# customESC_Test_Board.net
KiCad netlist of a schematic drawn in EAGLE
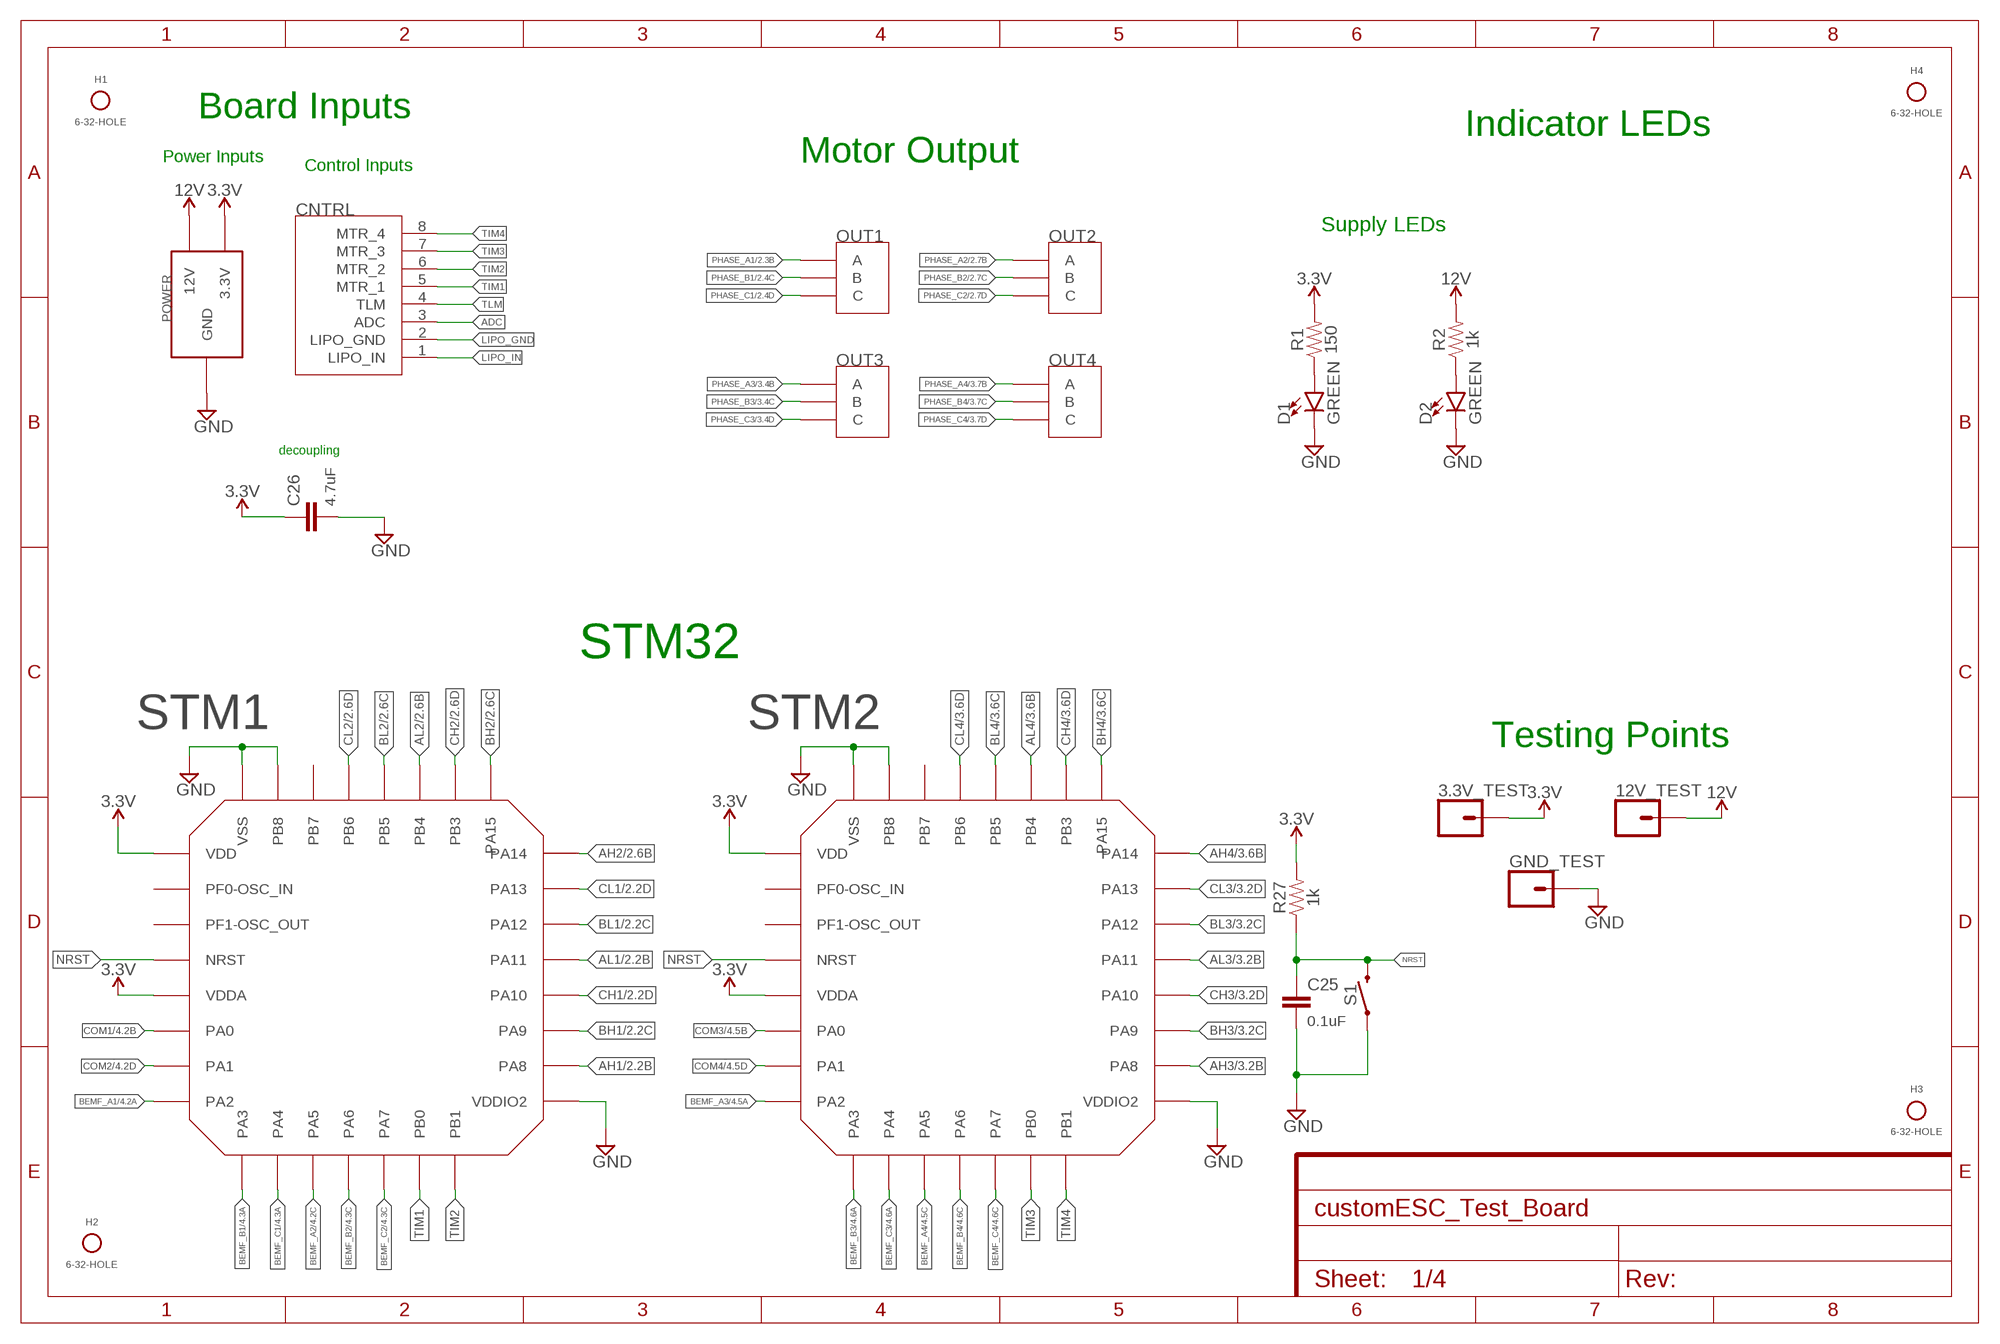
[diagram p0: schematic, sheet 1]
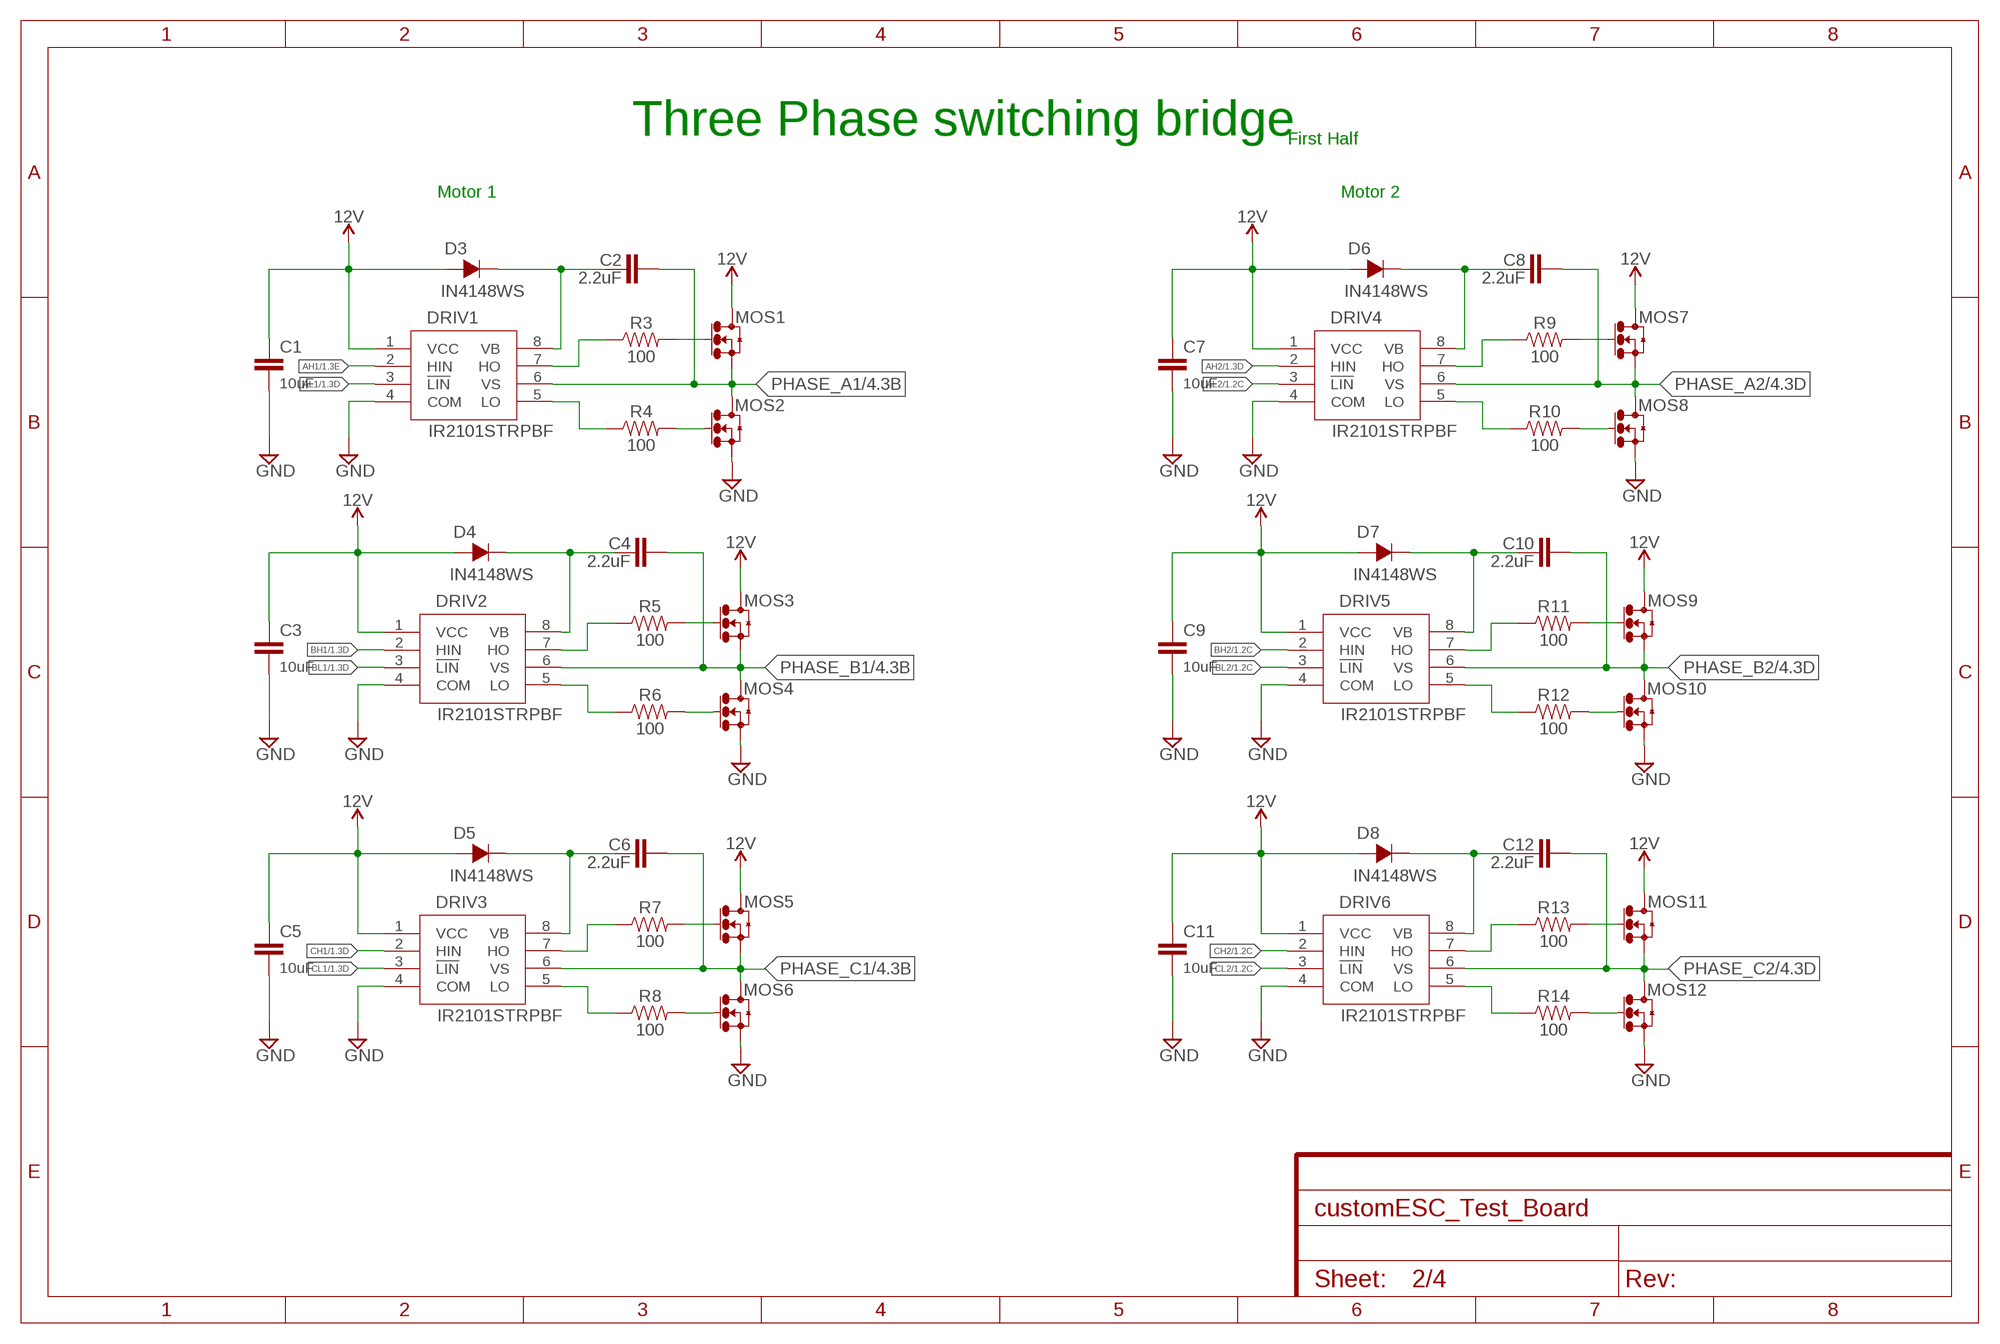
[diagram p1: schematic, sheet 2]
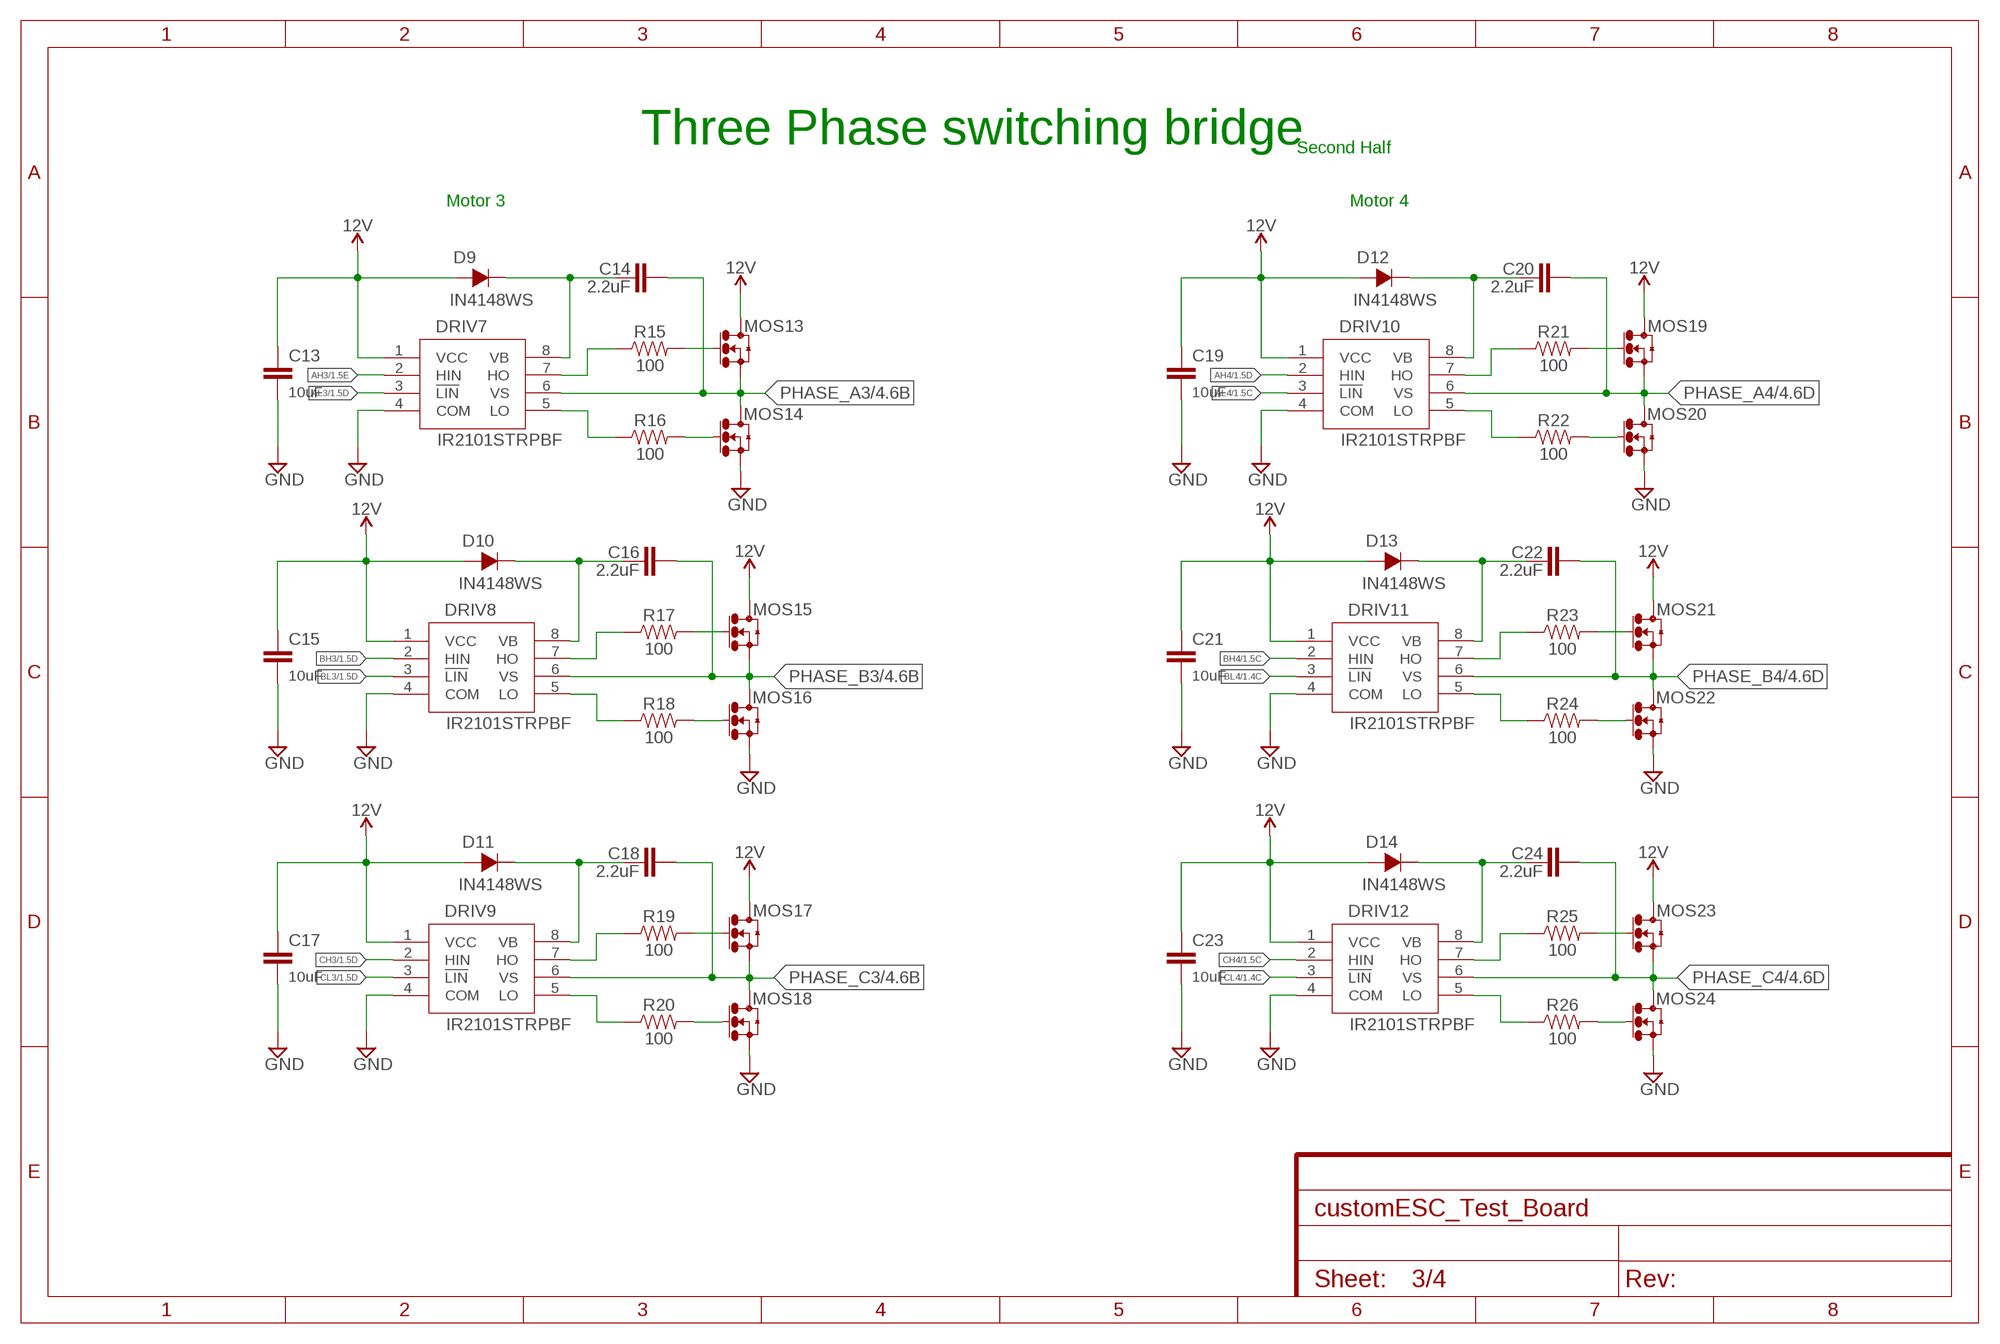
[diagram p2: schematic, sheet 3]
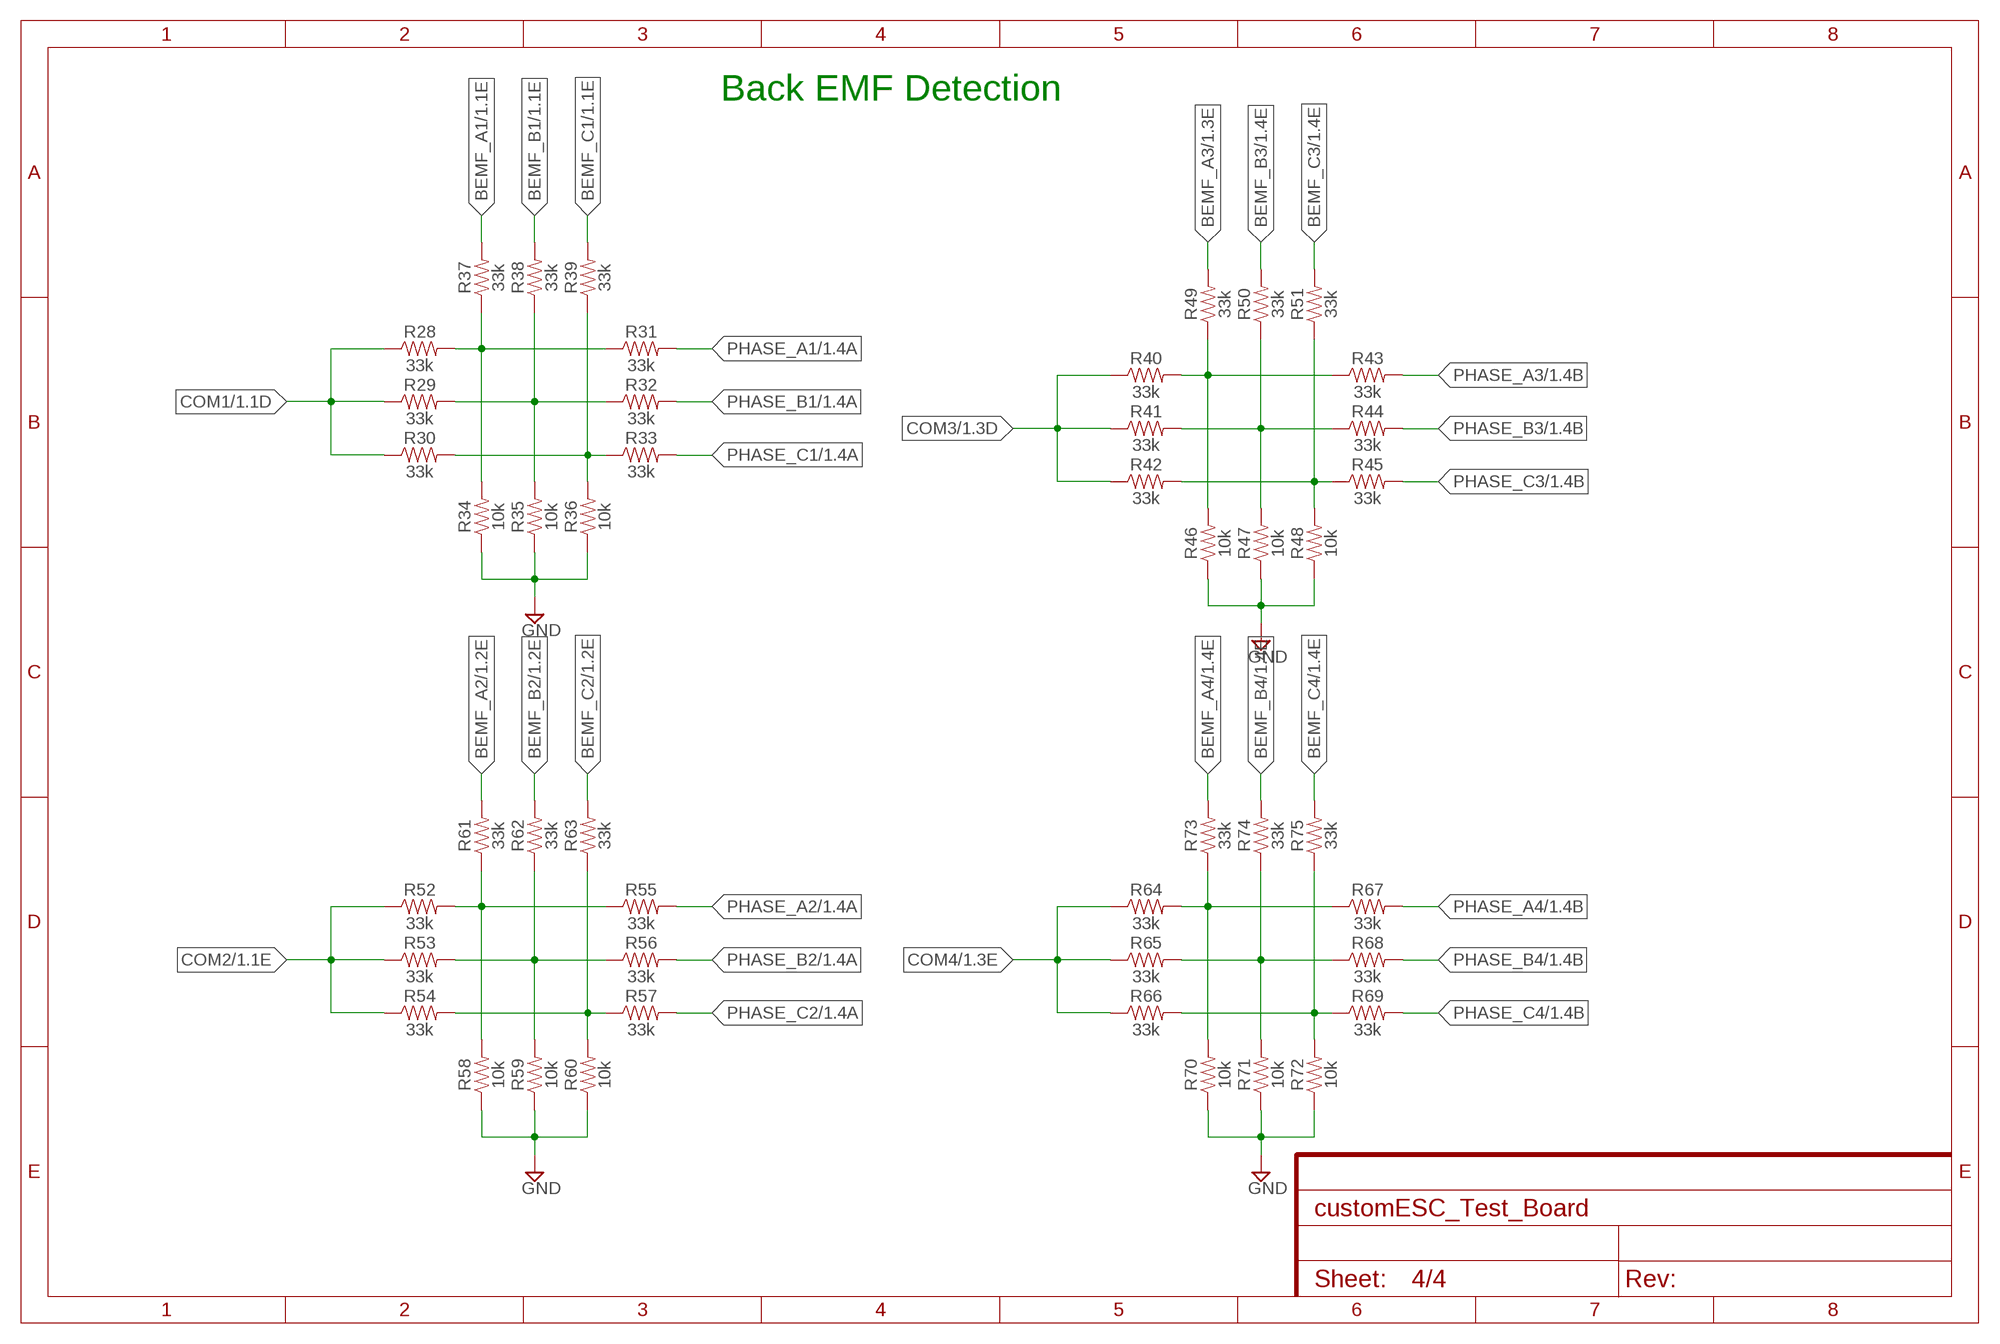
[diagram p3: schematic, sheet 4]

(export (version "E")
  (design (tool "Eeschema 10.0.6"))
  (components
    (comp (ref "C1")
      (value "10uF")
      (footprint "eagle-import:0603")
      (libsource (lib "eagle-import") (part "10UF-0603-6.3V-20%"))
    )
    (comp (ref "C2")
      (value "2.2uF")
      (footprint "eagle-import:0603")
      (libsource (lib "eagle-import") (part "10UF-0603-6.3V-20%"))
    )
    (comp (ref "C3")
      (value "10uF")
      (footprint "eagle-import:0603")
      (libsource (lib "eagle-import") (part "10UF-0603-6.3V-20%"))
    )
    (comp (ref "C4")
      (value "2.2uF")
      (footprint "eagle-import:0603")
      (libsource (lib "eagle-import") (part "10UF-0603-6.3V-20%"))
    )
    (comp (ref "C5")
      (value "10uF")
      (footprint "eagle-import:0603")
      (libsource (lib "eagle-import") (part "10UF-0603-6.3V-20%"))
    )
    (comp (ref "C6")
      (value "2.2uF")
      (footprint "eagle-import:0603")
      (libsource (lib "eagle-import") (part "10UF-0603-6.3V-20%"))
    )
    (comp (ref "C7")
      (value "10uF")
      (footprint "eagle-import:0603")
      (libsource (lib "eagle-import") (part "10UF-0603-6.3V-20%"))
    )
    (comp (ref "C8")
      (value "2.2uF")
      (footprint "eagle-import:0603")
      (libsource (lib "eagle-import") (part "10UF-0603-6.3V-20%"))
    )
    (comp (ref "C9")
      (value "10uF")
      (footprint "eagle-import:0603")
      (libsource (lib "eagle-import") (part "10UF-0603-6.3V-20%"))
    )
    (comp (ref "C10")
      (value "2.2uF")
      (footprint "eagle-import:0603")
      (libsource (lib "eagle-import") (part "10UF-0603-6.3V-20%"))
    )
    (comp (ref "C11")
      (value "10uF")
      (footprint "eagle-import:0603")
      (libsource (lib "eagle-import") (part "10UF-0603-6.3V-20%"))
    )
    (comp (ref "C12")
      (value "2.2uF")
      (footprint "eagle-import:0603")
      (libsource (lib "eagle-import") (part "10UF-0603-6.3V-20%"))
    )
    (comp (ref "D3")
      (value "IN4148WS")
      (footprint "eagle-import:IN4148WS")
      (libsource (lib "eagle-import") (part "IN4148WS"))
    )
    (comp (ref "D4")
      (value "IN4148WS")
      (footprint "eagle-import:IN4148WS")
      (libsource (lib "eagle-import") (part "IN4148WS"))
    )
    (comp (ref "D5")
      (value "IN4148WS")
      (footprint "eagle-import:IN4148WS")
      (libsource (lib "eagle-import") (part "IN4148WS"))
    )
    (comp (ref "D6")
      (value "IN4148WS")
      (footprint "eagle-import:IN4148WS")
      (libsource (lib "eagle-import") (part "IN4148WS"))
    )
    (comp (ref "D7")
      (value "IN4148WS")
      (footprint "eagle-import:IN4148WS")
      (libsource (lib "eagle-import") (part "IN4148WS"))
    )
    (comp (ref "D8")
      (value "IN4148WS")
      (footprint "eagle-import:IN4148WS")
      (libsource (lib "eagle-import") (part "IN4148WS"))
    )
    (comp (ref "DRIV1")
      (value "IR2101STRPBF")
      (footprint "eagle-import:IR2101STRPBF")
      (libsource (lib "eagle-import") (part "IR2101STRPBF"))
    )
    (comp (ref "DRIV2")
      (value "IR2101STRPBF")
      (footprint "eagle-import:IR2101STRPBF")
      (libsource (lib "eagle-import") (part "IR2101STRPBF"))
    )
    (comp (ref "DRIV3")
      (value "IR2101STRPBF")
      (footprint "eagle-import:IR2101STRPBF")
      (libsource (lib "eagle-import") (part "IR2101STRPBF"))
    )
    (comp (ref "DRIV4")
      (value "IR2101STRPBF")
      (footprint "eagle-import:IR2101STRPBF")
      (libsource (lib "eagle-import") (part "IR2101STRPBF"))
    )
    (comp (ref "DRIV5")
      (value "IR2101STRPBF")
      (footprint "eagle-import:IR2101STRPBF")
      (libsource (lib "eagle-import") (part "IR2101STRPBF"))
    )
    (comp (ref "DRIV6")
      (value "IR2101STRPBF")
      (footprint "eagle-import:IR2101STRPBF")
      (libsource (lib "eagle-import") (part "IR2101STRPBF"))
    )
    (comp (ref "MOS1")
      (value "IRLR7843TRPBF")
      (footprint "eagle-import:IRLR7843TRPBF")
      (libsource (lib "eagle-import") (part "IRLR7843TRPBF"))
    )
    (comp (ref "MOS2")
      (value "IRLR7843TRPBF")
      (footprint "eagle-import:IRLR7843TRPBF")
      (libsource (lib "eagle-import") (part "IRLR7843TRPBF"))
    )
    (comp (ref "MOS3")
      (value "IRLR7843TRPBF")
      (footprint "eagle-import:IRLR7843TRPBF")
      (libsource (lib "eagle-import") (part "IRLR7843TRPBF"))
    )
    (comp (ref "MOS4")
      (value "IRLR7843TRPBF")
      (footprint "eagle-import:IRLR7843TRPBF")
      (libsource (lib "eagle-import") (part "IRLR7843TRPBF"))
    )
    (comp (ref "MOS5")
      (value "IRLR7843TRPBF")
      (footprint "eagle-import:IRLR7843TRPBF")
      (libsource (lib "eagle-import") (part "IRLR7843TRPBF"))
    )
    (comp (ref "MOS6")
      (value "IRLR7843TRPBF")
      (footprint "eagle-import:IRLR7843TRPBF")
      (libsource (lib "eagle-import") (part "IRLR7843TRPBF"))
    )
    (comp (ref "MOS7")
      (value "IRLR7843TRPBF")
      (footprint "eagle-import:IRLR7843TRPBF")
      (libsource (lib "eagle-import") (part "IRLR7843TRPBF"))
    )
    (comp (ref "MOS8")
      (value "IRLR7843TRPBF")
      (footprint "eagle-import:IRLR7843TRPBF")
      (libsource (lib "eagle-import") (part "IRLR7843TRPBF"))
    )
    (comp (ref "MOS9")
      (value "IRLR7843TRPBF")
      (footprint "eagle-import:IRLR7843TRPBF")
      (libsource (lib "eagle-import") (part "IRLR7843TRPBF"))
    )
    (comp (ref "MOS10")
      (value "IRLR7843TRPBF")
      (footprint "eagle-import:IRLR7843TRPBF")
      (libsource (lib "eagle-import") (part "IRLR7843TRPBF"))
    )
    (comp (ref "MOS11")
      (value "IRLR7843TRPBF")
      (footprint "eagle-import:IRLR7843TRPBF")
      (libsource (lib "eagle-import") (part "IRLR7843TRPBF"))
    )
    (comp (ref "MOS12")
      (value "IRLR7843TRPBF")
      (footprint "eagle-import:IRLR7843TRPBF")
      (libsource (lib "eagle-import") (part "IRLR7843TRPBF"))
    )
    (comp (ref "R3")
      (value "100")
      (footprint "eagle-import:0603")
      (libsource (lib "eagle-import") (part "1KOHM-0603-1/10W-1%"))
    )
    (comp (ref "R4")
      (value "100")
      (footprint "eagle-import:0603")
      (libsource (lib "eagle-import") (part "1KOHM-0603-1/10W-1%"))
    )
    (comp (ref "R5")
      (value "100")
      (footprint "eagle-import:0603")
      (libsource (lib "eagle-import") (part "1KOHM-0603-1/10W-1%"))
    )
    (comp (ref "R6")
      (value "100")
      (footprint "eagle-import:0603")
      (libsource (lib "eagle-import") (part "1KOHM-0603-1/10W-1%"))
    )
    (comp (ref "R7")
      (value "100")
      (footprint "eagle-import:0603")
      (libsource (lib "eagle-import") (part "1KOHM-0603-1/10W-1%"))
    )
    (comp (ref "R8")
      (value "100")
      (footprint "eagle-import:0603")
      (libsource (lib "eagle-import") (part "1KOHM-0603-1/10W-1%"))
    )
    (comp (ref "R9")
      (value "100")
      (footprint "eagle-import:0603")
      (libsource (lib "eagle-import") (part "1KOHM-0603-1/10W-1%"))
    )
    (comp (ref "R10")
      (value "100")
      (footprint "eagle-import:0603")
      (libsource (lib "eagle-import") (part "1KOHM-0603-1/10W-1%"))
    )
    (comp (ref "R11")
      (value "100")
      (footprint "eagle-import:0603")
      (libsource (lib "eagle-import") (part "1KOHM-0603-1/10W-1%"))
    )
    (comp (ref "R12")
      (value "100")
      (footprint "eagle-import:0603")
      (libsource (lib "eagle-import") (part "1KOHM-0603-1/10W-1%"))
    )
    (comp (ref "R13")
      (value "100")
      (footprint "eagle-import:0603")
      (libsource (lib "eagle-import") (part "1KOHM-0603-1/10W-1%"))
    )
    (comp (ref "R14")
      (value "100")
      (footprint "eagle-import:0603")
      (libsource (lib "eagle-import") (part "1KOHM-0603-1/10W-1%"))
    )
    (comp (ref "R28")
      (value "33k")
      (footprint "eagle-import:0603")
      (libsource (lib "eagle-import") (part "1KOHM-0603-1/10W-1%"))
    )
    (comp (ref "R29")
      (value "33k")
      (footprint "eagle-import:0603")
      (libsource (lib "eagle-import") (part "1KOHM-0603-1/10W-1%"))
    )
    (comp (ref "R30")
      (value "33k")
      (footprint "eagle-import:0603")
      (libsource (lib "eagle-import") (part "1KOHM-0603-1/10W-1%"))
    )
    (comp (ref "R31")
      (value "33k")
      (footprint "eagle-import:0603")
      (libsource (lib "eagle-import") (part "1KOHM-0603-1/10W-1%"))
    )
    (comp (ref "R32")
      (value "33k")
      (footprint "eagle-import:0603")
      (libsource (lib "eagle-import") (part "1KOHM-0603-1/10W-1%"))
    )
    (comp (ref "R33")
      (value "33k")
      (footprint "eagle-import:0603")
      (libsource (lib "eagle-import") (part "1KOHM-0603-1/10W-1%"))
    )
    (comp (ref "R34")
      (value "10k")
      (footprint "eagle-import:0603")
      (libsource (lib "eagle-import") (part "1KOHM-0603-1/10W-1%"))
    )
    (comp (ref "R35")
      (value "10k")
      (footprint "eagle-import:0603")
      (libsource (lib "eagle-import") (part "1KOHM-0603-1/10W-1%"))
    )
    (comp (ref "R36")
      (value "10k")
      (footprint "eagle-import:0603")
      (libsource (lib "eagle-import") (part "1KOHM-0603-1/10W-1%"))
    )
    (comp (ref "R37")
      (value "33k")
      (footprint "eagle-import:0603")
      (libsource (lib "eagle-import") (part "1KOHM-0603-1/10W-1%"))
    )
    (comp (ref "R38")
      (value "33k")
      (footprint "eagle-import:0603")
      (libsource (lib "eagle-import") (part "1KOHM-0603-1/10W-1%"))
    )
    (comp (ref "R39")
      (value "33k")
      (footprint "eagle-import:0603")
      (libsource (lib "eagle-import") (part "1KOHM-0603-1/10W-1%"))
    )
    (comp (ref "R40")
      (value "33k")
      (footprint "eagle-import:0603")
      (libsource (lib "eagle-import") (part "1KOHM-0603-1/10W-1%"))
    )
    (comp (ref "R41")
      (value "33k")
      (footprint "eagle-import:0603")
      (libsource (lib "eagle-import") (part "1KOHM-0603-1/10W-1%"))
    )
    (comp (ref "R42")
      (value "33k")
      (footprint "eagle-import:0603")
      (libsource (lib "eagle-import") (part "1KOHM-0603-1/10W-1%"))
    )
    (comp (ref "R43")
      (value "33k")
      (footprint "eagle-import:0603")
      (libsource (lib "eagle-import") (part "1KOHM-0603-1/10W-1%"))
    )
    (comp (ref "R44")
      (value "33k")
      (footprint "eagle-import:0603")
      (libsource (lib "eagle-import") (part "1KOHM-0603-1/10W-1%"))
    )
    (comp (ref "R45")
      (value "33k")
      (footprint "eagle-import:0603")
      (libsource (lib "eagle-import") (part "1KOHM-0603-1/10W-1%"))
    )
    (comp (ref "R46")
      (value "10k")
      (footprint "eagle-import:0603")
      (libsource (lib "eagle-import") (part "1KOHM-0603-1/10W-1%"))
    )
    (comp (ref "R47")
      (value "10k")
      (footprint "eagle-import:0603")
      (libsource (lib "eagle-import") (part "1KOHM-0603-1/10W-1%"))
    )
    (comp (ref "R48")
      (value "10k")
      (footprint "eagle-import:0603")
      (libsource (lib "eagle-import") (part "1KOHM-0603-1/10W-1%"))
    )
    (comp (ref "R49")
      (value "33k")
      (footprint "eagle-import:0603")
      (libsource (lib "eagle-import") (part "1KOHM-0603-1/10W-1%"))
    )
    (comp (ref "R50")
      (value "33k")
      (footprint "eagle-import:0603")
      (libsource (lib "eagle-import") (part "1KOHM-0603-1/10W-1%"))
    )
    (comp (ref "R51")
      (value "33k")
      (footprint "eagle-import:0603")
      (libsource (lib "eagle-import") (part "1KOHM-0603-1/10W-1%"))
    )
    (comp (ref "R52")
      (value "33k")
      (footprint "eagle-import:0603")
      (libsource (lib "eagle-import") (part "1KOHM-0603-1/10W-1%"))
    )
    (comp (ref "R53")
      (value "33k")
      (footprint "eagle-import:0603")
      (libsource (lib "eagle-import") (part "1KOHM-0603-1/10W-1%"))
    )
    (comp (ref "R54")
      (value "33k")
      (footprint "eagle-import:0603")
      (libsource (lib "eagle-import") (part "1KOHM-0603-1/10W-1%"))
    )
    (comp (ref "R55")
      (value "33k")
      (footprint "eagle-import:0603")
      (libsource (lib "eagle-import") (part "1KOHM-0603-1/10W-1%"))
    )
    (comp (ref "R56")
      (value "33k")
      (footprint "eagle-import:0603")
      (libsource (lib "eagle-import") (part "1KOHM-0603-1/10W-1%"))
    )
    (comp (ref "R57")
      (value "33k")
      (footprint "eagle-import:0603")
      (libsource (lib "eagle-import") (part "1KOHM-0603-1/10W-1%"))
    )
    (comp (ref "R58")
      (value "10k")
      (footprint "eagle-import:0603")
      (libsource (lib "eagle-import") (part "1KOHM-0603-1/10W-1%"))
    )
    (comp (ref "R59")
      (value "10k")
      (footprint "eagle-import:0603")
      (libsource (lib "eagle-import") (part "1KOHM-0603-1/10W-1%"))
    )
    (comp (ref "R60")
      (value "10k")
      (footprint "eagle-import:0603")
      (libsource (lib "eagle-import") (part "1KOHM-0603-1/10W-1%"))
    )
    (comp (ref "R61")
      (value "33k")
      (footprint "eagle-import:0603")
      (libsource (lib "eagle-import") (part "1KOHM-0603-1/10W-1%"))
    )
    (comp (ref "R62")
      (value "33k")
      (footprint "eagle-import:0603")
      (libsource (lib "eagle-import") (part "1KOHM-0603-1/10W-1%"))
    )
    (comp (ref "R63")
      (value "33k")
      (footprint "eagle-import:0603")
      (libsource (lib "eagle-import") (part "1KOHM-0603-1/10W-1%"))
    )
    (comp (ref "R64")
      (value "33k")
      (footprint "eagle-import:0603")
      (libsource (lib "eagle-import") (part "1KOHM-0603-1/10W-1%"))
    )
    (comp (ref "R65")
      (value "33k")
      (footprint "eagle-import:0603")
      (libsource (lib "eagle-import") (part "1KOHM-0603-1/10W-1%"))
    )
    (comp (ref "R66")
      (value "33k")
      (footprint "eagle-import:0603")
      (libsource (lib "eagle-import") (part "1KOHM-0603-1/10W-1%"))
    )
    (comp (ref "R67")
      (value "33k")
      (footprint "eagle-import:0603")
      (libsource (lib "eagle-import") (part "1KOHM-0603-1/10W-1%"))
    )
    (comp (ref "R68")
      (value "33k")
      (footprint "eagle-import:0603")
      (libsource (lib "eagle-import") (part "1KOHM-0603-1/10W-1%"))
    )
    (comp (ref "R69")
      (value "33k")
      (footprint "eagle-import:0603")
      (libsource (lib "eagle-import") (part "1KOHM-0603-1/10W-1%"))
    )
    (comp (ref "R70")
      (value "10k")
      (footprint "eagle-import:0603")
      (libsource (lib "eagle-import") (part "1KOHM-0603-1/10W-1%"))
    )
    (comp (ref "R71")
      (value "10k")
      (footprint "eagle-import:0603")
      (libsource (lib "eagle-import") (part "1KOHM-0603-1/10W-1%"))
    )
    (comp (ref "R72")
      (value "10k")
      (footprint "eagle-import:0603")
      (libsource (lib "eagle-import") (part "1KOHM-0603-1/10W-1%"))
    )
    (comp (ref "R73")
      (value "33k")
      (footprint "eagle-import:0603")
      (libsource (lib "eagle-import") (part "1KOHM-0603-1/10W-1%"))
    )
    (comp (ref "R74")
      (value "33k")
      (footprint "eagle-import:0603")
      (libsource (lib "eagle-import") (part "1KOHM-0603-1/10W-1%"))
    )
    (comp (ref "R75")
      (value "33k")
      (footprint "eagle-import:0603")
      (libsource (lib "eagle-import") (part "1KOHM-0603-1/10W-1%"))
    )
    (comp (ref "C13")
      (value "10uF")
      (footprint "eagle-import:0603")
      (libsource (lib "eagle-import") (part "10UF-0603-6.3V-20%"))
    )
    (comp (ref "C14")
      (value "2.2uF")
      (footprint "eagle-import:0603")
      (libsource (lib "eagle-import") (part "10UF-0603-6.3V-20%"))
    )
    (comp (ref "C15")
      (value "10uF")
      (footprint "eagle-import:0603")
      (libsource (lib "eagle-import") (part "10UF-0603-6.3V-20%"))
    )
    (comp (ref "C16")
      (value "2.2uF")
      (footprint "eagle-import:0603")
      (libsource (lib "eagle-import") (part "10UF-0603-6.3V-20%"))
    )
    (comp (ref "C17")
      (value "10uF")
      (footprint "eagle-import:0603")
      (libsource (lib "eagle-import") (part "10UF-0603-6.3V-20%"))
    )
    (comp (ref "C18")
      (value "2.2uF")
      (footprint "eagle-import:0603")
      (libsource (lib "eagle-import") (part "10UF-0603-6.3V-20%"))
    )
    (comp (ref "C19")
      (value "10uF")
      (footprint "eagle-import:0603")
      (libsource (lib "eagle-import") (part "10UF-0603-6.3V-20%"))
    )
    (comp (ref "C20")
      (value "2.2uF")
      (footprint "eagle-import:0603")
      (libsource (lib "eagle-import") (part "10UF-0603-6.3V-20%"))
    )
    (comp (ref "C21")
      (value "10uF")
      (footprint "eagle-import:0603")
      (libsource (lib "eagle-import") (part "10UF-0603-6.3V-20%"))
    )
    (comp (ref "C22")
      (value "2.2uF")
      (footprint "eagle-import:0603")
      (libsource (lib "eagle-import") (part "10UF-0603-6.3V-20%"))
    )
    (comp (ref "C23")
      (value "10uF")
      (footprint "eagle-import:0603")
      (libsource (lib "eagle-import") (part "10UF-0603-6.3V-20%"))
    )
    (comp (ref "C24")
      (value "2.2uF")
      (footprint "eagle-import:0603")
      (libsource (lib "eagle-import") (part "10UF-0603-6.3V-20%"))
    )
    (comp (ref "D9")
      (value "IN4148WS")
      (footprint "eagle-import:IN4148WS")
      (libsource (lib "eagle-import") (part "IN4148WS"))
    )
    (comp (ref "D10")
      (value "IN4148WS")
      (footprint "eagle-import:IN4148WS")
      (libsource (lib "eagle-import") (part "IN4148WS"))
    )
    (comp (ref "D11")
      (value "IN4148WS")
      (footprint "eagle-import:IN4148WS")
      (libsource (lib "eagle-import") (part "IN4148WS"))
    )
    (comp (ref "D12")
      (value "IN4148WS")
      (footprint "eagle-import:IN4148WS")
      (libsource (lib "eagle-import") (part "IN4148WS"))
    )
    (comp (ref "D13")
      (value "IN4148WS")
      (footprint "eagle-import:IN4148WS")
      (libsource (lib "eagle-import") (part "IN4148WS"))
    )
    (comp (ref "D14")
      (value "IN4148WS")
      (footprint "eagle-import:IN4148WS")
      (libsource (lib "eagle-import") (part "IN4148WS"))
    )
    (comp (ref "DRIV7")
      (value "IR2101STRPBF")
      (footprint "eagle-import:IR2101STRPBF")
      (libsource (lib "eagle-import") (part "IR2101STRPBF"))
    )
    (comp (ref "DRIV8")
      (value "IR2101STRPBF")
      (footprint "eagle-import:IR2101STRPBF")
      (libsource (lib "eagle-import") (part "IR2101STRPBF"))
    )
    (comp (ref "DRIV9")
      (value "IR2101STRPBF")
      (footprint "eagle-import:IR2101STRPBF")
      (libsource (lib "eagle-import") (part "IR2101STRPBF"))
    )
    (comp (ref "DRIV10")
      (value "IR2101STRPBF")
      (footprint "eagle-import:IR2101STRPBF")
      (libsource (lib "eagle-import") (part "IR2101STRPBF"))
    )
    (comp (ref "DRIV11")
      (value "IR2101STRPBF")
      (footprint "eagle-import:IR2101STRPBF")
      (libsource (lib "eagle-import") (part "IR2101STRPBF"))
    )
    (comp (ref "DRIV12")
      (value "IR2101STRPBF")
      (footprint "eagle-import:IR2101STRPBF")
      (libsource (lib "eagle-import") (part "IR2101STRPBF"))
    )
    (comp (ref "MOS13")
      (value "IRLR7843TRPBF")
      (footprint "eagle-import:IRLR7843TRPBF")
      (libsource (lib "eagle-import") (part "IRLR7843TRPBF"))
    )
    (comp (ref "MOS14")
      (value "IRLR7843TRPBF")
      (footprint "eagle-import:IRLR7843TRPBF")
      (libsource (lib "eagle-import") (part "IRLR7843TRPBF"))
    )
    (comp (ref "MOS15")
      (value "IRLR7843TRPBF")
      (footprint "eagle-import:IRLR7843TRPBF")
      (libsource (lib "eagle-import") (part "IRLR7843TRPBF"))
    )
    (comp (ref "MOS16")
      (value "IRLR7843TRPBF")
      (footprint "eagle-import:IRLR7843TRPBF")
      (libsource (lib "eagle-import") (part "IRLR7843TRPBF"))
    )
    (comp (ref "MOS17")
      (value "IRLR7843TRPBF")
      (footprint "eagle-import:IRLR7843TRPBF")
      (libsource (lib "eagle-import") (part "IRLR7843TRPBF"))
    )
    (comp (ref "MOS18")
      (value "IRLR7843TRPBF")
      (footprint "eagle-import:IRLR7843TRPBF")
      (libsource (lib "eagle-import") (part "IRLR7843TRPBF"))
    )
    (comp (ref "MOS19")
      (value "IRLR7843TRPBF")
      (footprint "eagle-import:IRLR7843TRPBF")
      (libsource (lib "eagle-import") (part "IRLR7843TRPBF"))
    )
    (comp (ref "MOS20")
      (value "IRLR7843TRPBF")
      (footprint "eagle-import:IRLR7843TRPBF")
      (libsource (lib "eagle-import") (part "IRLR7843TRPBF"))
    )
    (comp (ref "MOS21")
      (value "IRLR7843TRPBF")
      (footprint "eagle-import:IRLR7843TRPBF")
      (libsource (lib "eagle-import") (part "IRLR7843TRPBF"))
    )
    (comp (ref "MOS22")
      (value "IRLR7843TRPBF")
      (footprint "eagle-import:IRLR7843TRPBF")
      (libsource (lib "eagle-import") (part "IRLR7843TRPBF"))
    )
    (comp (ref "MOS23")
      (value "IRLR7843TRPBF")
      (footprint "eagle-import:IRLR7843TRPBF")
      (libsource (lib "eagle-import") (part "IRLR7843TRPBF"))
    )
    (comp (ref "MOS24")
      (value "IRLR7843TRPBF")
      (footprint "eagle-import:IRLR7843TRPBF")
      (libsource (lib "eagle-import") (part "IRLR7843TRPBF"))
    )
    (comp (ref "R15")
      (value "100")
      (footprint "eagle-import:0603")
      (libsource (lib "eagle-import") (part "1KOHM-0603-1/10W-1%"))
    )
    (comp (ref "R16")
      (value "100")
      (footprint "eagle-import:0603")
      (libsource (lib "eagle-import") (part "1KOHM-0603-1/10W-1%"))
    )
    (comp (ref "R17")
      (value "100")
      (footprint "eagle-import:0603")
      (libsource (lib "eagle-import") (part "1KOHM-0603-1/10W-1%"))
    )
    (comp (ref "R18")
      (value "100")
      (footprint "eagle-import:0603")
      (libsource (lib "eagle-import") (part "1KOHM-0603-1/10W-1%"))
    )
    (comp (ref "R19")
      (value "100")
      (footprint "eagle-import:0603")
      (libsource (lib "eagle-import") (part "1KOHM-0603-1/10W-1%"))
    )
    (comp (ref "R20")
      (value "100")
      (footprint "eagle-import:0603")
      (libsource (lib "eagle-import") (part "1KOHM-0603-1/10W-1%"))
    )
    (comp (ref "R21")
      (value "100")
      (footprint "eagle-import:0603")
      (libsource (lib "eagle-import") (part "1KOHM-0603-1/10W-1%"))
    )
    (comp (ref "R22")
      (value "100")
      (footprint "eagle-import:0603")
      (libsource (lib "eagle-import") (part "1KOHM-0603-1/10W-1%"))
    )
    (comp (ref "R23")
      (value "100")
      (footprint "eagle-import:0603")
      (libsource (lib "eagle-import") (part "1KOHM-0603-1/10W-1%"))
    )
    (comp (ref "R24")
      (value "100")
      (footprint "eagle-import:0603")
      (libsource (lib "eagle-import") (part "1KOHM-0603-1/10W-1%"))
    )
    (comp (ref "R25")
      (value "100")
      (footprint "eagle-import:0603")
      (libsource (lib "eagle-import") (part "1KOHM-0603-1/10W-1%"))
    )
    (comp (ref "R26")
      (value "100")
      (footprint "eagle-import:0603")
      (libsource (lib "eagle-import") (part "1KOHM-0603-1/10W-1%"))
    )
    (comp (ref "3.3V_TEST")
      (value "CONN_01")
      (footprint "eagle-import:1X01")
      (libsource (lib "eagle-import") (part "CONN_01"))
    )
    (comp (ref "12V_TEST")
      (value "CONN_01")
      (footprint "eagle-import:1X01")
      (libsource (lib "eagle-import") (part "CONN_01"))
    )
    (comp (ref "C25")
      (value "0.1uF")
      (footprint "eagle-import:0603")
      (libsource (lib "eagle-import") (part "10UF-0603-6.3V-20%"))
    )
    (comp (ref "C26")
      (value "4.7uF")
      (footprint "eagle-import:0603")
      (libsource (lib "eagle-import") (part "10UF-0603-6.3V-20%"))
    )
    (comp (ref "CNTRL")
      (value "JST_8_PIN")
      (footprint "eagle-import:JST_8_PIN")
      (libsource (lib "eagle-import") (part "JST_8_PIN"))
    )
    (comp (ref "D1")
      (value "GREEN")
      (footprint "eagle-import:LED-0603")
      (libsource (lib "eagle-import") (part "LED-GREEN0603"))
    )
    (comp (ref "D2")
      (value "GREEN")
      (footprint "eagle-import:LED-0603")
      (libsource (lib "eagle-import") (part "LED-GREEN0603"))
    )
    (comp (ref "GND_TEST")
      (value "CONN_01")
      (footprint "eagle-import:1X01")
      (libsource (lib "eagle-import") (part "CONN_01"))
    )
    (comp (ref "H1")
      (value "6-32-HOLE")
      (footprint "eagle-import:MOUNTING_HOLE")
      (libsource (lib "eagle-import") (part "6-32-HOLE"))
    )
    (comp (ref "H2")
      (value "6-32-HOLE")
      (footprint "eagle-import:MOUNTING_HOLE")
      (libsource (lib "eagle-import") (part "6-32-HOLE"))
    )
    (comp (ref "H3")
      (value "6-32-HOLE")
      (footprint "eagle-import:MOUNTING_HOLE")
      (libsource (lib "eagle-import") (part "6-32-HOLE"))
    )
    (comp (ref "H4")
      (value "6-32-HOLE")
      (footprint "eagle-import:MOUNTING_HOLE")
      (libsource (lib "eagle-import") (part "6-32-HOLE"))
    )
    (comp (ref "OUT1")
      (value "IPBT-103-H1-T-S")
      (footprint "eagle-import:IPBT-103-H1-T-S")
      (libsource (lib "eagle-import") (part "IPBT-103-H1-T-S"))
    )
    (comp (ref "OUT2")
      (value "IPBT-103-H1-T-S")
      (footprint "eagle-import:IPBT-103-H1-T-S")
      (libsource (lib "eagle-import") (part "IPBT-103-H1-T-S"))
    )
    (comp (ref "OUT3")
      (value "IPBT-103-H1-T-S")
      (footprint "eagle-import:IPBT-103-H1-T-S")
      (libsource (lib "eagle-import") (part "IPBT-103-H1-T-S"))
    )
    (comp (ref "OUT4")
      (value "IPBT-103-H1-T-S")
      (footprint "eagle-import:IPBT-103-H1-T-S")
      (libsource (lib "eagle-import") (part "IPBT-103-H1-T-S"))
    )
    (comp (ref "POWER")
      (value "12V-CONNECTOR")
      (footprint "eagle-import:12V-CONNECTOR")
      (libsource (lib "eagle-import") (part "12V-CONNECTOR"))
    )
    (comp (ref "R1")
      (value "150")
      (footprint "eagle-import:0603")
      (libsource (lib "eagle-import") (part "1KOHM-0603-1/10W-1%"))
    )
    (comp (ref "R2")
      (value "1k")
      (footprint "eagle-import:0603")
      (libsource (lib "eagle-import") (part "1KOHM-0603-1/10W-1%"))
    )
    (comp (ref "R27")
      (value "1k")
      (footprint "eagle-import:0603")
      (libsource (lib "eagle-import") (part "1KOHM-0603-1/10W-1%"))
    )
    (comp (ref "S1")
      (value "MOMENTARY-SWITCH-SPST-SMD-6.0X3.5MM")
      (footprint "eagle-import:TACTILE_SWITCH_SMD_6.0X3.5MM")
      (libsource (lib "eagle-import") (part "MOMENTARY-SWITCH-SPST-SMD-6.0X3.5MM"))
    )
    (comp (ref "STM1")
      (value "STM32F042K6T6")
      (footprint "eagle-import:STM32F042K6T6")
      (libsource (lib "eagle-import") (part "STM32F042K6T6"))
    )
    (comp (ref "STM2")
      (value "STM32F042K6T6")
      (footprint "eagle-import:STM32F042K6T6")
      (libsource (lib "eagle-import") (part "STM32F042K6T6"))
    )
  )
  (nets
    (net (code "1") (name "ADC") (class "Default")
      (node (ref "CNTRL") (pin "3") (pinfunction "ADC_3") (pintype "bidirectional"))
    )
    (net (code "2") (name "AH1") (class "Default")
      (node (ref "DRIV1") (pin "2") (pinfunction "HIN_2") (pintype "bidirectional"))
      (node (ref "STM1") (pin "PA8") (pinfunction "PA8_PA8") (pintype "bidirectional"))
    )
    (net (code "3") (name "AH2") (class "Default")
      (node (ref "DRIV4") (pin "2") (pinfunction "HIN_2") (pintype "bidirectional"))
      (node (ref "STM1") (pin "PA14") (pinfunction "PA14_PA14") (pintype "bidirectional"))
    )
    (net (code "4") (name "AH3") (class "Default")
      (node (ref "DRIV7") (pin "2") (pinfunction "HIN_2") (pintype "bidirectional"))
      (node (ref "STM2") (pin "PA8") (pinfunction "PA8_PA8") (pintype "bidirectional"))
    )
    (net (code "5") (name "AH4") (class "Default")
      (node (ref "DRIV10") (pin "2") (pinfunction "HIN_2") (pintype "bidirectional"))
      (node (ref "STM2") (pin "PA14") (pinfunction "PA14_PA14") (pintype "bidirectional"))
    )
    (net (code "6") (name "AL1") (class "Default")
      (node (ref "DRIV1") (pin "3") (pinfunction "~{LIN}_3") (pintype "bidirectional"))
      (node (ref "STM1") (pin "PA11") (pinfunction "PA11_PA11") (pintype "bidirectional"))
    )
    (net (code "7") (name "AL2") (class "Default")
      (node (ref "DRIV4") (pin "3") (pinfunction "~{LIN}_3") (pintype "bidirectional"))
      (node (ref "STM1") (pin "PB4") (pinfunction "PB4_PB4") (pintype "bidirectional"))
    )
    (net (code "8") (name "AL3") (class "Default")
      (node (ref "DRIV7") (pin "3") (pinfunction "~{LIN}_3") (pintype "bidirectional"))
      (node (ref "STM2") (pin "PA11") (pinfunction "PA11_PA11") (pintype "bidirectional"))
    )
    (net (code "9") (name "AL4") (class "Default")
      (node (ref "DRIV10") (pin "3") (pinfunction "~{LIN}_3") (pintype "bidirectional"))
      (node (ref "STM2") (pin "PB4") (pinfunction "PB4_PB4") (pintype "bidirectional"))
    )
    (net (code "10") (name "BEMF_A1") (class "Default")
      (node (ref "R37") (pin "2") (pinfunction "2_2") (pintype "passive"))
      (node (ref "STM1") (pin "PA2") (pinfunction "PA2_PA2") (pintype "bidirectional"))
    )
    (net (code "11") (name "BEMF_A2") (class "Default")
      (node (ref "R61") (pin "2") (pinfunction "2_2") (pintype "passive"))
      (node (ref "STM1") (pin "PA5") (pinfunction "PA5_PA5") (pintype "bidirectional"))
    )
    (net (code "12") (name "BEMF_A3") (class "Default")
      (node (ref "R49") (pin "2") (pinfunction "2_2") (pintype "passive"))
      (node (ref "STM2") (pin "PA2") (pinfunction "PA2_PA2") (pintype "bidirectional"))
    )
    (net (code "13") (name "BEMF_A4") (class "Default")
      (node (ref "R73") (pin "2") (pinfunction "2_2") (pintype "passive"))
      (node (ref "STM2") (pin "PA5") (pinfunction "PA5_PA5") (pintype "bidirectional"))
    )
    (net (code "14") (name "BEMF_B1") (class "Default")
      (node (ref "R38") (pin "2") (pinfunction "2_2") (pintype "passive"))
      (node (ref "STM1") (pin "PA3") (pinfunction "PA3_PA3") (pintype "bidirectional"))
    )
    (net (code "15") (name "BEMF_B2") (class "Default")
      (node (ref "R62") (pin "2") (pinfunction "2_2") (pintype "passive"))
      (node (ref "STM1") (pin "PA6") (pinfunction "PA6_PA6") (pintype "bidirectional"))
    )
    (net (code "16") (name "BEMF_B3") (class "Default")
      (node (ref "R50") (pin "2") (pinfunction "2_2") (pintype "passive"))
      (node (ref "STM2") (pin "PA3") (pinfunction "PA3_PA3") (pintype "bidirectional"))
    )
    (net (code "17") (name "BEMF_B4") (class "Default")
      (node (ref "R74") (pin "2") (pinfunction "2_2") (pintype "passive"))
      (node (ref "STM2") (pin "PA6") (pinfunction "PA6_PA6") (pintype "bidirectional"))
    )
    (net (code "18") (name "BEMF_C1") (class "Default")
      (node (ref "R39") (pin "2") (pinfunction "2_2") (pintype "passive"))
      (node (ref "STM1") (pin "PA4") (pinfunction "PA4_PA4") (pintype "bidirectional"))
    )
    (net (code "19") (name "BEMF_C2") (class "Default")
      (node (ref "R63") (pin "2") (pinfunction "2_2") (pintype "passive"))
      (node (ref "STM1") (pin "PA7") (pinfunction "PA7_PA7") (pintype "bidirectional"))
    )
    (net (code "20") (name "BEMF_C3") (class "Default")
      (node (ref "R51") (pin "2") (pinfunction "2_2") (pintype "passive"))
      (node (ref "STM2") (pin "PA4") (pinfunction "PA4_PA4") (pintype "bidirectional"))
    )
    (net (code "21") (name "BEMF_C4") (class "Default")
      (node (ref "R75") (pin "2") (pinfunction "2_2") (pintype "passive"))
      (node (ref "STM2") (pin "PA7") (pinfunction "PA7_PA7") (pintype "bidirectional"))
    )
    (net (code "22") (name "BH1") (class "Default")
      (node (ref "DRIV2") (pin "2") (pinfunction "HIN_2") (pintype "bidirectional"))
      (node (ref "STM1") (pin "PA9") (pinfunction "PA9_PA9") (pintype "bidirectional"))
    )
    (net (code "23") (name "BH2") (class "Default")
      (node (ref "DRIV5") (pin "2") (pinfunction "HIN_2") (pintype "bidirectional"))
      (node (ref "STM1") (pin "PA15") (pinfunction "PA15_PA15") (pintype "bidirectional"))
    )
    (net (code "24") (name "BH3") (class "Default")
      (node (ref "DRIV8") (pin "2") (pinfunction "HIN_2") (pintype "bidirectional"))
      (node (ref "STM2") (pin "PA9") (pinfunction "PA9_PA9") (pintype "bidirectional"))
    )
    (net (code "25") (name "BH4") (class "Default")
      (node (ref "DRIV11") (pin "2") (pinfunction "HIN_2") (pintype "bidirectional"))
      (node (ref "STM2") (pin "PA15") (pinfunction "PA15_PA15") (pintype "bidirectional"))
    )
    (net (code "26") (name "BL1") (class "Default")
      (node (ref "DRIV2") (pin "3") (pinfunction "~{LIN}_3") (pintype "bidirectional"))
      (node (ref "STM1") (pin "PA12") (pinfunction "PA12_PA12") (pintype "bidirectional"))
    )
    (net (code "27") (name "BL2") (class "Default")
      (node (ref "DRIV5") (pin "3") (pinfunction "~{LIN}_3") (pintype "bidirectional"))
      (node (ref "STM1") (pin "PB5") (pinfunction "PB5_PB5") (pintype "bidirectional"))
    )
    (net (code "28") (name "BL3") (class "Default")
      (node (ref "DRIV8") (pin "3") (pinfunction "~{LIN}_3") (pintype "bidirectional"))
      (node (ref "STM2") (pin "PA12") (pinfunction "PA12_PA12") (pintype "bidirectional"))
    )
    (net (code "29") (name "BL4") (class "Default")
      (node (ref "DRIV11") (pin "3") (pinfunction "~{LIN}_3") (pintype "bidirectional"))
      (node (ref "STM2") (pin "PB5") (pinfunction "PB5_PB5") (pintype "bidirectional"))
    )
    (net (code "30") (name "CH1") (class "Default")
      (node (ref "DRIV3") (pin "2") (pinfunction "HIN_2") (pintype "bidirectional"))
      (node (ref "STM1") (pin "PA10") (pinfunction "PA10_PA10") (pintype "bidirectional"))
    )
    (net (code "31") (name "CH2") (class "Default")
      (node (ref "DRIV6") (pin "2") (pinfunction "HIN_2") (pintype "bidirectional"))
      (node (ref "STM1") (pin "PB3") (pinfunction "PB3_PB3") (pintype "bidirectional"))
    )
    (net (code "32") (name "CH3") (class "Default")
      (node (ref "DRIV9") (pin "2") (pinfunction "HIN_2") (pintype "bidirectional"))
      (node (ref "STM2") (pin "PA10") (pinfunction "PA10_PA10") (pintype "bidirectional"))
    )
    (net (code "33") (name "CH4") (class "Default")
      (node (ref "DRIV12") (pin "2") (pinfunction "HIN_2") (pintype "bidirectional"))
      (node (ref "STM2") (pin "PB3") (pinfunction "PB3_PB3") (pintype "bidirectional"))
    )
    (net (code "34") (name "CL1") (class "Default")
      (node (ref "DRIV3") (pin "3") (pinfunction "~{LIN}_3") (pintype "bidirectional"))
      (node (ref "STM1") (pin "PA13") (pinfunction "PA13_PA13") (pintype "bidirectional"))
    )
    (net (code "35") (name "CL2") (class "Default")
      (node (ref "DRIV6") (pin "3") (pinfunction "~{LIN}_3") (pintype "bidirectional"))
      (node (ref "STM1") (pin "PB6") (pinfunction "PB6_PB6") (pintype "bidirectional"))
    )
    (net (code "36") (name "CL3") (class "Default")
      (node (ref "DRIV9") (pin "3") (pinfunction "~{LIN}_3") (pintype "bidirectional"))
      (node (ref "STM2") (pin "PA13") (pinfunction "PA13_PA13") (pintype "bidirectional"))
    )
    (net (code "37") (name "CL4") (class "Default")
      (node (ref "DRIV12") (pin "3") (pinfunction "~{LIN}_3") (pintype "bidirectional"))
      (node (ref "STM2") (pin "PB6") (pinfunction "PB6_PB6") (pintype "bidirectional"))
    )
    (net (code "38") (name "COM1") (class "Default")
      (node (ref "R28") (pin "1") (pinfunction "1_1") (pintype "passive"))
      (node (ref "R29") (pin "1") (pinfunction "1_1") (pintype "passive"))
      (node (ref "R30") (pin "1") (pinfunction "1_1") (pintype "passive"))
      (node (ref "STM1") (pin "PA0") (pinfunction "PA0_PA0") (pintype "bidirectional"))
    )
    (net (code "39") (name "COM2") (class "Default")
      (node (ref "R52") (pin "1") (pinfunction "1_1") (pintype "passive"))
      (node (ref "R53") (pin "1") (pinfunction "1_1") (pintype "passive"))
      (node (ref "R54") (pin "1") (pinfunction "1_1") (pintype "passive"))
      (node (ref "STM1") (pin "PA1") (pinfunction "PA1_PA1") (pintype "bidirectional"))
    )
    (net (code "40") (name "COM3") (class "Default")
      (node (ref "R40") (pin "1") (pinfunction "1_1") (pintype "passive"))
      (node (ref "R41") (pin "1") (pinfunction "1_1") (pintype "passive"))
      (node (ref "R42") (pin "1") (pinfunction "1_1") (pintype "passive"))
      (node (ref "STM2") (pin "PA0") (pinfunction "PA0_PA0") (pintype "bidirectional"))
    )
    (net (code "41") (name "COM4") (class "Default")
      (node (ref "R64") (pin "1") (pinfunction "1_1") (pintype "passive"))
      (node (ref "R65") (pin "1") (pinfunction "1_1") (pintype "passive"))
      (node (ref "R66") (pin "1") (pinfunction "1_1") (pintype "passive"))
      (node (ref "STM2") (pin "PA1") (pinfunction "PA1_PA1") (pintype "bidirectional"))
    )
    (net (code "42") (name "GND") (class "Default")
      (node (ref "C1") (pin "2") (pinfunction "2_2") (pintype "passive"))
      (node (ref "C11") (pin "2") (pinfunction "2_2") (pintype "passive"))
      (node (ref "C13") (pin "2") (pinfunction "2_2") (pintype "passive"))
      (node (ref "C15") (pin "2") (pinfunction "2_2") (pintype "passive"))
      (node (ref "C17") (pin "2") (pinfunction "2_2") (pintype "passive"))
      (node (ref "C19") (pin "2") (pinfunction "2_2") (pintype "passive"))
      (node (ref "C21") (pin "2") (pinfunction "2_2") (pintype "passive"))
      (node (ref "C23") (pin "2") (pinfunction "2_2") (pintype "passive"))
      (node (ref "C25") (pin "2") (pinfunction "2_2") (pintype "passive"))
      (node (ref "C26") (pin "2") (pinfunction "2_2") (pintype "passive"))
      (node (ref "C3") (pin "2") (pinfunction "2_2") (pintype "passive"))
      (node (ref "C5") (pin "2") (pinfunction "2_2") (pintype "passive"))
      (node (ref "C7") (pin "2") (pinfunction "2_2") (pintype "passive"))
      (node (ref "C9") (pin "2") (pinfunction "2_2") (pintype "passive"))
      (node (ref "D1") (pin "C") (pinfunction "C_C") (pintype "passive"))
      (node (ref "D2") (pin "C") (pinfunction "C_C") (pintype "passive"))
      (node (ref "DRIV1") (pin "4") (pinfunction "COM_4") (pintype "bidirectional"))
      (node (ref "DRIV10") (pin "4") (pinfunction "COM_4") (pintype "bidirectional"))
      (node (ref "DRIV11") (pin "4") (pinfunction "COM_4") (pintype "bidirectional"))
      (node (ref "DRIV12") (pin "4") (pinfunction "COM_4") (pintype "bidirectional"))
      (node (ref "DRIV2") (pin "4") (pinfunction "COM_4") (pintype "bidirectional"))
      (node (ref "DRIV3") (pin "4") (pinfunction "COM_4") (pintype "bidirectional"))
      (node (ref "DRIV4") (pin "4") (pinfunction "COM_4") (pintype "bidirectional"))
      (node (ref "DRIV5") (pin "4") (pinfunction "COM_4") (pintype "bidirectional"))
      (node (ref "DRIV6") (pin "4") (pinfunction "COM_4") (pintype "bidirectional"))
      (node (ref "DRIV7") (pin "4") (pinfunction "COM_4") (pintype "bidirectional"))
      (node (ref "DRIV8") (pin "4") (pinfunction "COM_4") (pintype "bidirectional"))
      (node (ref "DRIV9") (pin "4") (pinfunction "COM_4") (pintype "bidirectional"))
      (node (ref "GND_TEST") (pin "1") (pinfunction "1_1") (pintype "passive"))
      (node (ref "MOS10") (pin "2") (pinfunction "DRAIN_2") (pintype "bidirectional"))
      (node (ref "MOS10") (pin "4") (pinfunction "DRAIN_4") (pintype "bidirectional"))
      (node (ref "MOS12") (pin "2") (pinfunction "DRAIN_2") (pintype "bidirectional"))
      (node (ref "MOS12") (pin "4") (pinfunction "DRAIN_4") (pintype "bidirectional"))
      (node (ref "MOS14") (pin "2") (pinfunction "DRAIN_2") (pintype "bidirectional"))
      (node (ref "MOS14") (pin "4") (pinfunction "DRAIN_4") (pintype "bidirectional"))
      (node (ref "MOS16") (pin "2") (pinfunction "DRAIN_2") (pintype "bidirectional"))
      (node (ref "MOS16") (pin "4") (pinfunction "DRAIN_4") (pintype "bidirectional"))
      (node (ref "MOS18") (pin "2") (pinfunction "DRAIN_2") (pintype "bidirectional"))
      (node (ref "MOS18") (pin "4") (pinfunction "DRAIN_4") (pintype "bidirectional"))
      (node (ref "MOS2") (pin "2") (pinfunction "DRAIN_2") (pintype "bidirectional"))
      (node (ref "MOS2") (pin "4") (pinfunction "DRAIN_4") (pintype "bidirectional"))
      (node (ref "MOS20") (pin "2") (pinfunction "DRAIN_2") (pintype "bidirectional"))
      (node (ref "MOS20") (pin "4") (pinfunction "DRAIN_4") (pintype "bidirectional"))
      (node (ref "MOS22") (pin "2") (pinfunction "DRAIN_2") (pintype "bidirectional"))
      (node (ref "MOS22") (pin "4") (pinfunction "DRAIN_4") (pintype "bidirectional"))
      (node (ref "MOS24") (pin "2") (pinfunction "DRAIN_2") (pintype "bidirectional"))
      (node (ref "MOS24") (pin "4") (pinfunction "DRAIN_4") (pintype "bidirectional"))
      (node (ref "MOS4") (pin "2") (pinfunction "DRAIN_2") (pintype "bidirectional"))
      (node (ref "MOS4") (pin "4") (pinfunction "DRAIN_4") (pintype "bidirectional"))
      (node (ref "MOS6") (pin "2") (pinfunction "DRAIN_2") (pintype "bidirectional"))
      (node (ref "MOS6") (pin "4") (pinfunction "DRAIN_4") (pintype "bidirectional"))
      (node (ref "MOS8") (pin "2") (pinfunction "DRAIN_2") (pintype "bidirectional"))
      (node (ref "MOS8") (pin "4") (pinfunction "DRAIN_4") (pintype "bidirectional"))
      (node (ref "POWER") (pin "GND") (pinfunction "GND_GND") (pintype "bidirectional"))
      (node (ref "POWER") (pin "GND@1") (pinfunction "GND_GND@1") (pintype "bidirectional"))
      (node (ref "POWER") (pin "GND@10") (pinfunction "GND_GND@10") (pintype "bidirectional"))
      (node (ref "POWER") (pin "GND@11") (pinfunction "GND_GND@11") (pintype "bidirectional"))
      (node (ref "POWER") (pin "GND@12") (pinfunction "GND_GND@12") (pintype "bidirectional"))
      (node (ref "POWER") (pin "GND@2") (pinfunction "GND_GND@2") (pintype "bidirectional"))
      (node (ref "POWER") (pin "GND@3") (pinfunction "GND_GND@3") (pintype "bidirectional"))
      (node (ref "POWER") (pin "GND@4") (pinfunction "GND_GND@4") (pintype "bidirectional"))
      (node (ref "POWER") (pin "GND@5") (pinfunction "GND_GND@5") (pintype "bidirectional"))
      (node (ref "POWER") (pin "GND@6") (pinfunction "GND_GND@6") (pintype "bidirectional"))
      (node (ref "POWER") (pin "GND@7") (pinfunction "GND_GND@7") (pintype "bidirectional"))
      (node (ref "POWER") (pin "GND@8") (pinfunction "GND_GND@8") (pintype "bidirectional"))
      (node (ref "POWER") (pin "GND@9") (pinfunction "GND_GND@9") (pintype "bidirectional"))
      (node (ref "R34") (pin "1") (pinfunction "1_1") (pintype "passive"))
      (node (ref "R35") (pin "1") (pinfunction "1_1") (pintype "passive"))
      (node (ref "R36") (pin "1") (pinfunction "1_1") (pintype "passive"))
      (node (ref "R46") (pin "1") (pinfunction "1_1") (pintype "passive"))
      (node (ref "R47") (pin "1") (pinfunction "1_1") (pintype "passive"))
      (node (ref "R48") (pin "1") (pinfunction "1_1") (pintype "passive"))
      (node (ref "R58") (pin "1") (pinfunction "1_1") (pintype "passive"))
      (node (ref "R59") (pin "1") (pinfunction "1_1") (pintype "passive"))
      (node (ref "R60") (pin "1") (pinfunction "1_1") (pintype "passive"))
      (node (ref "R70") (pin "1") (pinfunction "1_1") (pintype "passive"))
      (node (ref "R71") (pin "1") (pinfunction "1_1") (pintype "passive"))
      (node (ref "R72") (pin "1") (pinfunction "1_1") (pintype "passive"))
      (node (ref "S1") (pin "1") (pinfunction "1_1") (pintype "passive"))
      (node (ref "STM1") (pin "PB8-BOOT0") (pinfunction "PB8_PB8-BOOT0") (pintype "bidirectional"))
      (node (ref "STM1") (pin "VDDIO2") (pinfunction "VDDIO2_VDDIO2") (pintype "bidirectional"))
      (node (ref "STM1") (pin "VSS") (pinfunction "VSS_VSS") (pintype "bidirectional"))
      (node (ref "STM1") (pin "VSS1") (pinfunction "VSS_VSS1") (pintype "bidirectional"))
      (node (ref "STM2") (pin "PB8-BOOT0") (pinfunction "PB8_PB8-BOOT0") (pintype "bidirectional"))
      (node (ref "STM2") (pin "VDDIO2") (pinfunction "VDDIO2_VDDIO2") (pintype "bidirectional"))
      (node (ref "STM2") (pin "VSS") (pinfunction "VSS_VSS") (pintype "bidirectional"))
      (node (ref "STM2") (pin "VSS1") (pinfunction "VSS_VSS1") (pintype "bidirectional"))
    )
    (net (code "43") (name "LIPO_GND") (class "Default")
      (node (ref "CNTRL") (pin "2") (pinfunction "LIPO_GND_2") (pintype "bidirectional"))
    )
    (net (code "44") (name "LIPO_IN") (class "Default")
      (node (ref "CNTRL") (pin "1") (pinfunction "LIPO_IN_1") (pintype "bidirectional"))
    )
    (net (code "45") (name "NRST") (class "Default")
      (node (ref "C25") (pin "1") (pinfunction "1_1") (pintype "passive"))
      (node (ref "R27") (pin "1") (pinfunction "1_1") (pintype "passive"))
      (node (ref "S1") (pin "2") (pinfunction "2_2") (pintype "passive"))
      (node (ref "STM1") (pin "NRST") (pinfunction "NRST_NRST") (pintype "bidirectional"))
      (node (ref "STM2") (pin "NRST") (pinfunction "NRST_NRST") (pintype "bidirectional"))
    )
    (net (code "46") (name "Net-(D1-PadA)") (class "Default")
      (node (ref "D1") (pin "A") (pinfunction "A_A") (pintype "passive"))
      (node (ref "R1") (pin "1") (pinfunction "1_1") (pintype "passive"))
    )
    (net (code "47") (name "Net-(D2-PadA)") (class "Default")
      (node (ref "D2") (pin "A") (pinfunction "A_A") (pintype "passive"))
      (node (ref "R2") (pin "1") (pinfunction "1_1") (pintype "passive"))
    )
    (net (code "48") (name "Net-(DRIV1-HO)") (class "Default")
      (node (ref "DRIV1") (pin "7") (pinfunction "HO_7") (pintype "bidirectional"))
      (node (ref "R3") (pin "1") (pinfunction "1_1") (pintype "passive"))
    )
    (net (code "49") (name "Net-(DRIV1-LO)") (class "Default")
      (node (ref "DRIV1") (pin "5") (pinfunction "LO_5") (pintype "bidirectional"))
      (node (ref "R4") (pin "1") (pinfunction "1_1") (pintype "passive"))
    )
    (net (code "50") (name "Net-(DRIV1-VB)") (class "Default")
      (node (ref "C2") (pin "1") (pinfunction "1_1") (pintype "passive"))
      (node (ref "D3") (pin "P$2") (pinfunction "P$2_P$2") (pintype "bidirectional"))
      (node (ref "DRIV1") (pin "8") (pinfunction "VB_8") (pintype "bidirectional"))
    )
    (net (code "51") (name "Net-(DRIV2-HO)") (class "Default")
      (node (ref "DRIV2") (pin "7") (pinfunction "HO_7") (pintype "bidirectional"))
      (node (ref "R5") (pin "1") (pinfunction "1_1") (pintype "passive"))
    )
    (net (code "52") (name "Net-(DRIV2-LO)") (class "Default")
      (node (ref "DRIV2") (pin "5") (pinfunction "LO_5") (pintype "bidirectional"))
      (node (ref "R6") (pin "1") (pinfunction "1_1") (pintype "passive"))
    )
    (net (code "53") (name "Net-(DRIV2-VB)") (class "Default")
      (node (ref "C4") (pin "1") (pinfunction "1_1") (pintype "passive"))
      (node (ref "D4") (pin "P$2") (pinfunction "P$2_P$2") (pintype "bidirectional"))
      (node (ref "DRIV2") (pin "8") (pinfunction "VB_8") (pintype "bidirectional"))
    )
    (net (code "54") (name "Net-(DRIV3-HO)") (class "Default")
      (node (ref "DRIV3") (pin "7") (pinfunction "HO_7") (pintype "bidirectional"))
      (node (ref "R7") (pin "1") (pinfunction "1_1") (pintype "passive"))
    )
    (net (code "55") (name "Net-(DRIV3-LO)") (class "Default")
      (node (ref "DRIV3") (pin "5") (pinfunction "LO_5") (pintype "bidirectional"))
      (node (ref "R8") (pin "1") (pinfunction "1_1") (pintype "passive"))
    )
    (net (code "56") (name "Net-(DRIV3-VB)") (class "Default")
      (node (ref "C6") (pin "1") (pinfunction "1_1") (pintype "passive"))
      (node (ref "D5") (pin "P$2") (pinfunction "P$2_P$2") (pintype "bidirectional"))
      (node (ref "DRIV3") (pin "8") (pinfunction "VB_8") (pintype "bidirectional"))
    )
    (net (code "57") (name "Net-(DRIV4-HO)") (class "Default")
      (node (ref "DRIV4") (pin "7") (pinfunction "HO_7") (pintype "bidirectional"))
      (node (ref "R9") (pin "1") (pinfunction "1_1") (pintype "passive"))
    )
    (net (code "58") (name "Net-(DRIV4-LO)") (class "Default")
      (node (ref "DRIV4") (pin "5") (pinfunction "LO_5") (pintype "bidirectional"))
      (node (ref "R10") (pin "1") (pinfunction "1_1") (pintype "passive"))
    )
    (net (code "59") (name "Net-(DRIV4-VB)") (class "Default")
      (node (ref "C8") (pin "1") (pinfunction "1_1") (pintype "passive"))
      (node (ref "D6") (pin "P$2") (pinfunction "P$2_P$2") (pintype "bidirectional"))
      (node (ref "DRIV4") (pin "8") (pinfunction "VB_8") (pintype "bidirectional"))
    )
    (net (code "60") (name "Net-(DRIV5-HO)") (class "Default")
      (node (ref "DRIV5") (pin "7") (pinfunction "HO_7") (pintype "bidirectional"))
      (node (ref "R11") (pin "1") (pinfunction "1_1") (pintype "passive"))
    )
    (net (code "61") (name "Net-(DRIV5-LO)") (class "Default")
      (node (ref "DRIV5") (pin "5") (pinfunction "LO_5") (pintype "bidirectional"))
      (node (ref "R12") (pin "1") (pinfunction "1_1") (pintype "passive"))
    )
    (net (code "62") (name "Net-(DRIV5-VB)") (class "Default")
      (node (ref "C10") (pin "1") (pinfunction "1_1") (pintype "passive"))
      (node (ref "D7") (pin "P$2") (pinfunction "P$2_P$2") (pintype "bidirectional"))
      (node (ref "DRIV5") (pin "8") (pinfunction "VB_8") (pintype "bidirectional"))
    )
    (net (code "63") (name "Net-(DRIV6-HO)") (class "Default")
      (node (ref "DRIV6") (pin "7") (pinfunction "HO_7") (pintype "bidirectional"))
      (node (ref "R13") (pin "1") (pinfunction "1_1") (pintype "passive"))
    )
    (net (code "64") (name "Net-(DRIV6-LO)") (class "Default")
      (node (ref "DRIV6") (pin "5") (pinfunction "LO_5") (pintype "bidirectional"))
      (node (ref "R14") (pin "1") (pinfunction "1_1") (pintype "passive"))
    )
    (net (code "65") (name "Net-(DRIV6-VB)") (class "Default")
      (node (ref "C12") (pin "1") (pinfunction "1_1") (pintype "passive"))
      (node (ref "D8") (pin "P$2") (pinfunction "P$2_P$2") (pintype "bidirectional"))
      (node (ref "DRIV6") (pin "8") (pinfunction "VB_8") (pintype "bidirectional"))
    )
    (net (code "66") (name "Net-(DRIV7-HO)") (class "Default")
      (node (ref "DRIV7") (pin "7") (pinfunction "HO_7") (pintype "bidirectional"))
      (node (ref "R15") (pin "1") (pinfunction "1_1") (pintype "passive"))
    )
    (net (code "67") (name "Net-(DRIV7-LO)") (class "Default")
      (node (ref "DRIV7") (pin "5") (pinfunction "LO_5") (pintype "bidirectional"))
      (node (ref "R16") (pin "1") (pinfunction "1_1") (pintype "passive"))
    )
    (net (code "68") (name "Net-(DRIV7-VB)") (class "Default")
      (node (ref "C14") (pin "1") (pinfunction "1_1") (pintype "passive"))
      (node (ref "D9") (pin "P$2") (pinfunction "P$2_P$2") (pintype "bidirectional"))
      (node (ref "DRIV7") (pin "8") (pinfunction "VB_8") (pintype "bidirectional"))
    )
    (net (code "69") (name "Net-(DRIV8-HO)") (class "Default")
      (node (ref "DRIV8") (pin "7") (pinfunction "HO_7") (pintype "bidirectional"))
      (node (ref "R17") (pin "1") (pinfunction "1_1") (pintype "passive"))
    )
    (net (code "70") (name "Net-(DRIV8-LO)") (class "Default")
      (node (ref "DRIV8") (pin "5") (pinfunction "LO_5") (pintype "bidirectional"))
      (node (ref "R18") (pin "1") (pinfunction "1_1") (pintype "passive"))
    )
    (net (code "71") (name "Net-(DRIV8-VB)") (class "Default")
      (node (ref "C16") (pin "1") (pinfunction "1_1") (pintype "passive"))
      (node (ref "D10") (pin "P$2") (pinfunction "P$2_P$2") (pintype "bidirectional"))
      (node (ref "DRIV8") (pin "8") (pinfunction "VB_8") (pintype "bidirectional"))
    )
    (net (code "72") (name "Net-(DRIV9-HO)") (class "Default")
      (node (ref "DRIV9") (pin "7") (pinfunction "HO_7") (pintype "bidirectional"))
      (node (ref "R19") (pin "1") (pinfunction "1_1") (pintype "passive"))
    )
    (net (code "73") (name "Net-(DRIV9-LO)") (class "Default")
      (node (ref "DRIV9") (pin "5") (pinfunction "LO_5") (pintype "bidirectional"))
      (node (ref "R20") (pin "1") (pinfunction "1_1") (pintype "passive"))
    )
    (net (code "74") (name "Net-(DRIV9-VB)") (class "Default")
      (node (ref "C18") (pin "1") (pinfunction "1_1") (pintype "passive"))
      (node (ref "D11") (pin "P$2") (pinfunction "P$2_P$2") (pintype "bidirectional"))
      (node (ref "DRIV9") (pin "8") (pinfunction "VB_8") (pintype "bidirectional"))
    )
    (net (code "75") (name "Net-(DRIV10-HO)") (class "Default")
      (node (ref "DRIV10") (pin "7") (pinfunction "HO_7") (pintype "bidirectional"))
      (node (ref "R21") (pin "1") (pinfunction "1_1") (pintype "passive"))
    )
    (net (code "76") (name "Net-(DRIV10-LO)") (class "Default")
      (node (ref "DRIV10") (pin "5") (pinfunction "LO_5") (pintype "bidirectional"))
      (node (ref "R22") (pin "1") (pinfunction "1_1") (pintype "passive"))
    )
    (net (code "77") (name "Net-(DRIV10-VB)") (class "Default")
      (node (ref "C20") (pin "1") (pinfunction "1_1") (pintype "passive"))
      (node (ref "D12") (pin "P$2") (pinfunction "P$2_P$2") (pintype "bidirectional"))
      (node (ref "DRIV10") (pin "8") (pinfunction "VB_8") (pintype "bidirectional"))
    )
    (net (code "78") (name "Net-(DRIV11-HO)") (class "Default")
      (node (ref "DRIV11") (pin "7") (pinfunction "HO_7") (pintype "bidirectional"))
      (node (ref "R23") (pin "1") (pinfunction "1_1") (pintype "passive"))
    )
    (net (code "79") (name "Net-(DRIV11-LO)") (class "Default")
      (node (ref "DRIV11") (pin "5") (pinfunction "LO_5") (pintype "bidirectional"))
      (node (ref "R24") (pin "1") (pinfunction "1_1") (pintype "passive"))
    )
    (net (code "80") (name "Net-(DRIV11-VB)") (class "Default")
      (node (ref "C22") (pin "1") (pinfunction "1_1") (pintype "passive"))
      (node (ref "D13") (pin "P$2") (pinfunction "P$2_P$2") (pintype "bidirectional"))
      (node (ref "DRIV11") (pin "8") (pinfunction "VB_8") (pintype "bidirectional"))
    )
    (net (code "81") (name "Net-(DRIV12-HO)") (class "Default")
      (node (ref "DRIV12") (pin "7") (pinfunction "HO_7") (pintype "bidirectional"))
      (node (ref "R25") (pin "1") (pinfunction "1_1") (pintype "passive"))
    )
    (net (code "82") (name "Net-(DRIV12-LO)") (class "Default")
      (node (ref "DRIV12") (pin "5") (pinfunction "LO_5") (pintype "bidirectional"))
      (node (ref "R26") (pin "1") (pinfunction "1_1") (pintype "passive"))
    )
    (net (code "83") (name "Net-(DRIV12-VB)") (class "Default")
      (node (ref "C24") (pin "1") (pinfunction "1_1") (pintype "passive"))
      (node (ref "D14") (pin "P$2") (pinfunction "P$2_P$2") (pintype "bidirectional"))
      (node (ref "DRIV12") (pin "8") (pinfunction "VB_8") (pintype "bidirectional"))
    )
    (net (code "84") (name "Net-(MOS1-GATE)") (class "Default")
      (node (ref "MOS1") (pin "1") (pinfunction "GATE_1") (pintype "bidirectional"))
      (node (ref "R3") (pin "2") (pinfunction "2_2") (pintype "passive"))
    )
    (net (code "85") (name "Net-(MOS2-GATE)") (class "Default")
      (node (ref "MOS2") (pin "1") (pinfunction "GATE_1") (pintype "bidirectional"))
      (node (ref "R4") (pin "2") (pinfunction "2_2") (pintype "passive"))
    )
    (net (code "86") (name "Net-(MOS3-GATE)") (class "Default")
      (node (ref "MOS3") (pin "1") (pinfunction "GATE_1") (pintype "bidirectional"))
      (node (ref "R5") (pin "2") (pinfunction "2_2") (pintype "passive"))
    )
    (net (code "87") (name "Net-(MOS4-GATE)") (class "Default")
      (node (ref "MOS4") (pin "1") (pinfunction "GATE_1") (pintype "bidirectional"))
      (node (ref "R6") (pin "2") (pinfunction "2_2") (pintype "passive"))
    )
    (net (code "88") (name "Net-(MOS5-GATE)") (class "Default")
      (node (ref "MOS5") (pin "1") (pinfunction "GATE_1") (pintype "bidirectional"))
      (node (ref "R7") (pin "2") (pinfunction "2_2") (pintype "passive"))
    )
    (net (code "89") (name "Net-(MOS6-GATE)") (class "Default")
      (node (ref "MOS6") (pin "1") (pinfunction "GATE_1") (pintype "bidirectional"))
      (node (ref "R8") (pin "2") (pinfunction "2_2") (pintype "passive"))
    )
    (net (code "90") (name "Net-(MOS7-GATE)") (class "Default")
      (node (ref "MOS7") (pin "1") (pinfunction "GATE_1") (pintype "bidirectional"))
      (node (ref "R9") (pin "2") (pinfunction "2_2") (pintype "passive"))
    )
    (net (code "91") (name "Net-(MOS8-GATE)") (class "Default")
      (node (ref "MOS8") (pin "1") (pinfunction "GATE_1") (pintype "bidirectional"))
      (node (ref "R10") (pin "2") (pinfunction "2_2") (pintype "passive"))
    )
    (net (code "92") (name "Net-(MOS9-GATE)") (class "Default")
      (node (ref "MOS9") (pin "1") (pinfunction "GATE_1") (pintype "bidirectional"))
      (node (ref "R11") (pin "2") (pinfunction "2_2") (pintype "passive"))
    )
    (net (code "93") (name "Net-(MOS10-GATE)") (class "Default")
      (node (ref "MOS10") (pin "1") (pinfunction "GATE_1") (pintype "bidirectional"))
      (node (ref "R12") (pin "2") (pinfunction "2_2") (pintype "passive"))
    )
    (net (code "94") (name "Net-(MOS11-GATE)") (class "Default")
      (node (ref "MOS11") (pin "1") (pinfunction "GATE_1") (pintype "bidirectional"))
      (node (ref "R13") (pin "2") (pinfunction "2_2") (pintype "passive"))
    )
    (net (code "95") (name "Net-(MOS12-GATE)") (class "Default")
      (node (ref "MOS12") (pin "1") (pinfunction "GATE_1") (pintype "bidirectional"))
      (node (ref "R14") (pin "2") (pinfunction "2_2") (pintype "passive"))
    )
    (net (code "96") (name "Net-(MOS13-GATE)") (class "Default")
      (node (ref "MOS13") (pin "1") (pinfunction "GATE_1") (pintype "bidirectional"))
      (node (ref "R15") (pin "2") (pinfunction "2_2") (pintype "passive"))
    )
    (net (code "97") (name "Net-(MOS14-GATE)") (class "Default")
      (node (ref "MOS14") (pin "1") (pinfunction "GATE_1") (pintype "bidirectional"))
      (node (ref "R16") (pin "2") (pinfunction "2_2") (pintype "passive"))
    )
    (net (code "98") (name "Net-(MOS15-GATE)") (class "Default")
      (node (ref "MOS15") (pin "1") (pinfunction "GATE_1") (pintype "bidirectional"))
      (node (ref "R17") (pin "2") (pinfunction "2_2") (pintype "passive"))
    )
    (net (code "99") (name "Net-(MOS16-GATE)") (class "Default")
      (node (ref "MOS16") (pin "1") (pinfunction "GATE_1") (pintype "bidirectional"))
      (node (ref "R18") (pin "2") (pinfunction "2_2") (pintype "passive"))
    )
    (net (code "100") (name "Net-(MOS17-GATE)") (class "Default")
      (node (ref "MOS17") (pin "1") (pinfunction "GATE_1") (pintype "bidirectional"))
      (node (ref "R19") (pin "2") (pinfunction "2_2") (pintype "passive"))
    )
    (net (code "101") (name "Net-(MOS18-GATE)") (class "Default")
      (node (ref "MOS18") (pin "1") (pinfunction "GATE_1") (pintype "bidirectional"))
      (node (ref "R20") (pin "2") (pinfunction "2_2") (pintype "passive"))
    )
    (net (code "102") (name "Net-(MOS19-GATE)") (class "Default")
      (node (ref "MOS19") (pin "1") (pinfunction "GATE_1") (pintype "bidirectional"))
      (node (ref "R21") (pin "2") (pinfunction "2_2") (pintype "passive"))
    )
    (net (code "103") (name "Net-(MOS20-GATE)") (class "Default")
      (node (ref "MOS20") (pin "1") (pinfunction "GATE_1") (pintype "bidirectional"))
      (node (ref "R22") (pin "2") (pinfunction "2_2") (pintype "passive"))
    )
    (net (code "104") (name "Net-(MOS21-GATE)") (class "Default")
      (node (ref "MOS21") (pin "1") (pinfunction "GATE_1") (pintype "bidirectional"))
      (node (ref "R23") (pin "2") (pinfunction "2_2") (pintype "passive"))
    )
    (net (code "105") (name "Net-(MOS22-GATE)") (class "Default")
      (node (ref "MOS22") (pin "1") (pinfunction "GATE_1") (pintype "bidirectional"))
      (node (ref "R24") (pin "2") (pinfunction "2_2") (pintype "passive"))
    )
    (net (code "106") (name "Net-(MOS23-GATE)") (class "Default")
      (node (ref "MOS23") (pin "1") (pinfunction "GATE_1") (pintype "bidirectional"))
      (node (ref "R25") (pin "2") (pinfunction "2_2") (pintype "passive"))
    )
    (net (code "107") (name "Net-(MOS24-GATE)") (class "Default")
      (node (ref "MOS24") (pin "1") (pinfunction "GATE_1") (pintype "bidirectional"))
      (node (ref "R26") (pin "2") (pinfunction "2_2") (pintype "passive"))
    )
    (net (code "108") (name "Net-(R28-Pad2)") (class "Default")
      (node (ref "R28") (pin "2") (pinfunction "2_2") (pintype "passive"))
      (node (ref "R31") (pin "1") (pinfunction "1_1") (pintype "passive"))
      (node (ref "R34") (pin "2") (pinfunction "2_2") (pintype "passive"))
      (node (ref "R37") (pin "1") (pinfunction "1_1") (pintype "passive"))
    )
    (net (code "109") (name "Net-(R29-Pad2)") (class "Default")
      (node (ref "R29") (pin "2") (pinfunction "2_2") (pintype "passive"))
      (node (ref "R32") (pin "1") (pinfunction "1_1") (pintype "passive"))
      (node (ref "R35") (pin "2") (pinfunction "2_2") (pintype "passive"))
      (node (ref "R38") (pin "1") (pinfunction "1_1") (pintype "passive"))
    )
    (net (code "110") (name "Net-(R30-Pad2)") (class "Default")
      (node (ref "R30") (pin "2") (pinfunction "2_2") (pintype "passive"))
      (node (ref "R33") (pin "1") (pinfunction "1_1") (pintype "passive"))
      (node (ref "R36") (pin "2") (pinfunction "2_2") (pintype "passive"))
      (node (ref "R39") (pin "1") (pinfunction "1_1") (pintype "passive"))
    )
    (net (code "111") (name "Net-(R40-Pad2)") (class "Default")
      (node (ref "R40") (pin "2") (pinfunction "2_2") (pintype "passive"))
      (node (ref "R43") (pin "1") (pinfunction "1_1") (pintype "passive"))
      (node (ref "R46") (pin "2") (pinfunction "2_2") (pintype "passive"))
      (node (ref "R49") (pin "1") (pinfunction "1_1") (pintype "passive"))
    )
    (net (code "112") (name "Net-(R41-Pad2)") (class "Default")
      (node (ref "R41") (pin "2") (pinfunction "2_2") (pintype "passive"))
      (node (ref "R44") (pin "1") (pinfunction "1_1") (pintype "passive"))
      (node (ref "R47") (pin "2") (pinfunction "2_2") (pintype "passive"))
      (node (ref "R50") (pin "1") (pinfunction "1_1") (pintype "passive"))
    )
    (net (code "113") (name "Net-(R42-Pad2)") (class "Default")
      (node (ref "R42") (pin "2") (pinfunction "2_2") (pintype "passive"))
      (node (ref "R45") (pin "1") (pinfunction "1_1") (pintype "passive"))
      (node (ref "R48") (pin "2") (pinfunction "2_2") (pintype "passive"))
      (node (ref "R51") (pin "1") (pinfunction "1_1") (pintype "passive"))
    )
    (net (code "114") (name "Net-(R52-Pad2)") (class "Default")
      (node (ref "R52") (pin "2") (pinfunction "2_2") (pintype "passive"))
      (node (ref "R55") (pin "1") (pinfunction "1_1") (pintype "passive"))
      (node (ref "R58") (pin "2") (pinfunction "2_2") (pintype "passive"))
      (node (ref "R61") (pin "1") (pinfunction "1_1") (pintype "passive"))
    )
    (net (code "115") (name "Net-(R53-Pad2)") (class "Default")
      (node (ref "R53") (pin "2") (pinfunction "2_2") (pintype "passive"))
      (node (ref "R56") (pin "1") (pinfunction "1_1") (pintype "passive"))
      (node (ref "R59") (pin "2") (pinfunction "2_2") (pintype "passive"))
      (node (ref "R62") (pin "1") (pinfunction "1_1") (pintype "passive"))
    )
    (net (code "116") (name "Net-(R54-Pad2)") (class "Default")
      (node (ref "R54") (pin "2") (pinfunction "2_2") (pintype "passive"))
      (node (ref "R57") (pin "1") (pinfunction "1_1") (pintype "passive"))
      (node (ref "R60") (pin "2") (pinfunction "2_2") (pintype "passive"))
      (node (ref "R63") (pin "1") (pinfunction "1_1") (pintype "passive"))
    )
    (net (code "117") (name "Net-(R64-Pad2)") (class "Default")
      (node (ref "R64") (pin "2") (pinfunction "2_2") (pintype "passive"))
      (node (ref "R67") (pin "1") (pinfunction "1_1") (pintype "passive"))
      (node (ref "R70") (pin "2") (pinfunction "2_2") (pintype "passive"))
      (node (ref "R73") (pin "1") (pinfunction "1_1") (pintype "passive"))
    )
    (net (code "118") (name "Net-(R65-Pad2)") (class "Default")
      (node (ref "R65") (pin "2") (pinfunction "2_2") (pintype "passive"))
      (node (ref "R68") (pin "1") (pinfunction "1_1") (pintype "passive"))
      (node (ref "R71") (pin "2") (pinfunction "2_2") (pintype "passive"))
      (node (ref "R74") (pin "1") (pinfunction "1_1") (pintype "passive"))
    )
    (net (code "119") (name "Net-(R66-Pad2)") (class "Default")
      (node (ref "R66") (pin "2") (pinfunction "2_2") (pintype "passive"))
      (node (ref "R69") (pin "1") (pinfunction "1_1") (pintype "passive"))
      (node (ref "R72") (pin "2") (pinfunction "2_2") (pintype "passive"))
      (node (ref "R75") (pin "1") (pinfunction "1_1") (pintype "passive"))
    )
    (net (code "120") (name "PHASE_A1") (class "Default")
      (node (ref "C2") (pin "2") (pinfunction "2_2") (pintype "passive"))
      (node (ref "DRIV1") (pin "6") (pinfunction "VS_6") (pintype "bidirectional"))
      (node (ref "MOS1") (pin "2") (pinfunction "DRAIN_2") (pintype "bidirectional"))
      (node (ref "MOS1") (pin "4") (pinfunction "DRAIN_4") (pintype "bidirectional"))
      (node (ref "MOS2") (pin "3") (pinfunction "SOURCE_3") (pintype "bidirectional"))
      (node (ref "OUT1") (pin "1") (pinfunction "A_1") (pintype "bidirectional"))
      (node (ref "R31") (pin "2") (pinfunction "2_2") (pintype "passive"))
    )
    (net (code "121") (name "PHASE_A2") (class "Default")
      (node (ref "C8") (pin "2") (pinfunction "2_2") (pintype "passive"))
      (node (ref "DRIV4") (pin "6") (pinfunction "VS_6") (pintype "bidirectional"))
      (node (ref "MOS7") (pin "2") (pinfunction "DRAIN_2") (pintype "bidirectional"))
      (node (ref "MOS7") (pin "4") (pinfunction "DRAIN_4") (pintype "bidirectional"))
      (node (ref "MOS8") (pin "3") (pinfunction "SOURCE_3") (pintype "bidirectional"))
      (node (ref "OUT2") (pin "1") (pinfunction "A_1") (pintype "bidirectional"))
      (node (ref "R55") (pin "2") (pinfunction "2_2") (pintype "passive"))
    )
    (net (code "122") (name "PHASE_A3") (class "Default")
      (node (ref "C14") (pin "2") (pinfunction "2_2") (pintype "passive"))
      (node (ref "DRIV7") (pin "6") (pinfunction "VS_6") (pintype "bidirectional"))
      (node (ref "MOS13") (pin "2") (pinfunction "DRAIN_2") (pintype "bidirectional"))
      (node (ref "MOS13") (pin "4") (pinfunction "DRAIN_4") (pintype "bidirectional"))
      (node (ref "MOS14") (pin "3") (pinfunction "SOURCE_3") (pintype "bidirectional"))
      (node (ref "OUT3") (pin "1") (pinfunction "A_1") (pintype "bidirectional"))
      (node (ref "R43") (pin "2") (pinfunction "2_2") (pintype "passive"))
    )
    (net (code "123") (name "PHASE_A4") (class "Default")
      (node (ref "C20") (pin "2") (pinfunction "2_2") (pintype "passive"))
      (node (ref "DRIV10") (pin "6") (pinfunction "VS_6") (pintype "bidirectional"))
      (node (ref "MOS19") (pin "2") (pinfunction "DRAIN_2") (pintype "bidirectional"))
      (node (ref "MOS19") (pin "4") (pinfunction "DRAIN_4") (pintype "bidirectional"))
      (node (ref "MOS20") (pin "3") (pinfunction "SOURCE_3") (pintype "bidirectional"))
      (node (ref "OUT4") (pin "1") (pinfunction "A_1") (pintype "bidirectional"))
      (node (ref "R67") (pin "2") (pinfunction "2_2") (pintype "passive"))
    )
    (net (code "124") (name "PHASE_B1") (class "Default")
      (node (ref "C4") (pin "2") (pinfunction "2_2") (pintype "passive"))
      (node (ref "DRIV2") (pin "6") (pinfunction "VS_6") (pintype "bidirectional"))
      (node (ref "MOS3") (pin "2") (pinfunction "DRAIN_2") (pintype "bidirectional"))
      (node (ref "MOS3") (pin "4") (pinfunction "DRAIN_4") (pintype "bidirectional"))
      (node (ref "MOS4") (pin "3") (pinfunction "SOURCE_3") (pintype "bidirectional"))
      (node (ref "OUT1") (pin "2") (pinfunction "B_2") (pintype "bidirectional"))
      (node (ref "R32") (pin "2") (pinfunction "2_2") (pintype "passive"))
    )
    (net (code "125") (name "PHASE_B2") (class "Default")
      (node (ref "C10") (pin "2") (pinfunction "2_2") (pintype "passive"))
      (node (ref "DRIV5") (pin "6") (pinfunction "VS_6") (pintype "bidirectional"))
      (node (ref "MOS10") (pin "3") (pinfunction "SOURCE_3") (pintype "bidirectional"))
      (node (ref "MOS9") (pin "2") (pinfunction "DRAIN_2") (pintype "bidirectional"))
      (node (ref "MOS9") (pin "4") (pinfunction "DRAIN_4") (pintype "bidirectional"))
      (node (ref "OUT2") (pin "2") (pinfunction "B_2") (pintype "bidirectional"))
      (node (ref "R56") (pin "2") (pinfunction "2_2") (pintype "passive"))
    )
    (net (code "126") (name "PHASE_B3") (class "Default")
      (node (ref "C16") (pin "2") (pinfunction "2_2") (pintype "passive"))
      (node (ref "DRIV8") (pin "6") (pinfunction "VS_6") (pintype "bidirectional"))
      (node (ref "MOS15") (pin "2") (pinfunction "DRAIN_2") (pintype "bidirectional"))
      (node (ref "MOS15") (pin "4") (pinfunction "DRAIN_4") (pintype "bidirectional"))
      (node (ref "MOS16") (pin "3") (pinfunction "SOURCE_3") (pintype "bidirectional"))
      (node (ref "OUT3") (pin "2") (pinfunction "B_2") (pintype "bidirectional"))
      (node (ref "R44") (pin "2") (pinfunction "2_2") (pintype "passive"))
    )
    (net (code "127") (name "PHASE_B4") (class "Default")
      (node (ref "C22") (pin "2") (pinfunction "2_2") (pintype "passive"))
      (node (ref "DRIV11") (pin "6") (pinfunction "VS_6") (pintype "bidirectional"))
      (node (ref "MOS21") (pin "2") (pinfunction "DRAIN_2") (pintype "bidirectional"))
      (node (ref "MOS21") (pin "4") (pinfunction "DRAIN_4") (pintype "bidirectional"))
      (node (ref "MOS22") (pin "3") (pinfunction "SOURCE_3") (pintype "bidirectional"))
      (node (ref "OUT4") (pin "2") (pinfunction "B_2") (pintype "bidirectional"))
      (node (ref "R68") (pin "2") (pinfunction "2_2") (pintype "passive"))
    )
    (net (code "128") (name "PHASE_C1") (class "Default")
      (node (ref "C6") (pin "2") (pinfunction "2_2") (pintype "passive"))
      (node (ref "DRIV3") (pin "6") (pinfunction "VS_6") (pintype "bidirectional"))
      (node (ref "MOS5") (pin "2") (pinfunction "DRAIN_2") (pintype "bidirectional"))
      (node (ref "MOS5") (pin "4") (pinfunction "DRAIN_4") (pintype "bidirectional"))
      (node (ref "MOS6") (pin "3") (pinfunction "SOURCE_3") (pintype "bidirectional"))
      (node (ref "OUT1") (pin "3") (pinfunction "C_3") (pintype "bidirectional"))
      (node (ref "R33") (pin "2") (pinfunction "2_2") (pintype "passive"))
    )
    (net (code "129") (name "PHASE_C2") (class "Default")
      (node (ref "C12") (pin "2") (pinfunction "2_2") (pintype "passive"))
      (node (ref "DRIV6") (pin "6") (pinfunction "VS_6") (pintype "bidirectional"))
      (node (ref "MOS11") (pin "2") (pinfunction "DRAIN_2") (pintype "bidirectional"))
      (node (ref "MOS11") (pin "4") (pinfunction "DRAIN_4") (pintype "bidirectional"))
      (node (ref "MOS12") (pin "3") (pinfunction "SOURCE_3") (pintype "bidirectional"))
      (node (ref "OUT2") (pin "3") (pinfunction "C_3") (pintype "bidirectional"))
      (node (ref "R57") (pin "2") (pinfunction "2_2") (pintype "passive"))
    )
    (net (code "130") (name "PHASE_C3") (class "Default")
      (node (ref "C18") (pin "2") (pinfunction "2_2") (pintype "passive"))
      (node (ref "DRIV9") (pin "6") (pinfunction "VS_6") (pintype "bidirectional"))
      (node (ref "MOS17") (pin "2") (pinfunction "DRAIN_2") (pintype "bidirectional"))
      (node (ref "MOS17") (pin "4") (pinfunction "DRAIN_4") (pintype "bidirectional"))
      (node (ref "MOS18") (pin "3") (pinfunction "SOURCE_3") (pintype "bidirectional"))
      (node (ref "OUT3") (pin "3") (pinfunction "C_3") (pintype "bidirectional"))
      (node (ref "R45") (pin "2") (pinfunction "2_2") (pintype "passive"))
    )
    (net (code "131") (name "PHASE_C4") (class "Default")
      (node (ref "C24") (pin "2") (pinfunction "2_2") (pintype "passive"))
      (node (ref "DRIV12") (pin "6") (pinfunction "VS_6") (pintype "bidirectional"))
      (node (ref "MOS23") (pin "2") (pinfunction "DRAIN_2") (pintype "bidirectional"))
      (node (ref "MOS23") (pin "4") (pinfunction "DRAIN_4") (pintype "bidirectional"))
      (node (ref "MOS24") (pin "3") (pinfunction "SOURCE_3") (pintype "bidirectional"))
      (node (ref "OUT4") (pin "3") (pinfunction "C_3") (pintype "bidirectional"))
      (node (ref "R69") (pin "2") (pinfunction "2_2") (pintype "passive"))
    )
    (net (code "132") (name "TIM1") (class "Default")
      (node (ref "CNTRL") (pin "5") (pinfunction "MTR_1_5") (pintype "bidirectional"))
      (node (ref "STM1") (pin "PB0") (pinfunction "PB0_PB0") (pintype "bidirectional"))
    )
    (net (code "133") (name "TIM2") (class "Default")
      (node (ref "CNTRL") (pin "6") (pinfunction "MTR_2_6") (pintype "bidirectional"))
      (node (ref "STM1") (pin "PB1") (pinfunction "PB1_PB1") (pintype "bidirectional"))
    )
    (net (code "134") (name "TIM3") (class "Default")
      (node (ref "CNTRL") (pin "7") (pinfunction "MTR_3_7") (pintype "bidirectional"))
      (node (ref "STM2") (pin "PB0") (pinfunction "PB0_PB0") (pintype "bidirectional"))
    )
    (net (code "135") (name "TIM4") (class "Default")
      (node (ref "CNTRL") (pin "8") (pinfunction "MTR_4_8") (pintype "bidirectional"))
      (node (ref "STM2") (pin "PB1") (pinfunction "PB1_PB1") (pintype "bidirectional"))
    )
    (net (code "136") (name "TLM") (class "Default")
      (node (ref "CNTRL") (pin "4") (pinfunction "TLM_4") (pintype "bidirectional"))
    )
    (net (code "137") (name "VCC_1") (class "Default")
      (node (ref "3.3V_TEST") (pin "1") (pinfunction "1_1") (pintype "passive"))
      (node (ref "C26") (pin "1") (pinfunction "1_1") (pintype "passive"))
      (node (ref "POWER") (pin "3.3V") (pinfunction "3.3V_3.3V") (pintype "bidirectional"))
      (node (ref "R1") (pin "2") (pinfunction "2_2") (pintype "passive"))
      (node (ref "R27") (pin "2") (pinfunction "2_2") (pintype "passive"))
      (node (ref "STM1") (pin "VDD") (pinfunction "VDD_VDD") (pintype "bidirectional"))
      (node (ref "STM1") (pin "VDDA") (pinfunction "VDDA_VDDA") (pintype "bidirectional"))
      (node (ref "STM2") (pin "VDD") (pinfunction "VDD_VDD") (pintype "bidirectional"))
      (node (ref "STM2") (pin "VDDA") (pinfunction "VDDA_VDDA") (pintype "bidirectional"))
    )
    (net (code "138") (name "VCC_2") (class "Default")
      (node (ref "12V_TEST") (pin "1") (pinfunction "1_1") (pintype "passive"))
      (node (ref "C1") (pin "1") (pinfunction "1_1") (pintype "passive"))
      (node (ref "C11") (pin "1") (pinfunction "1_1") (pintype "passive"))
      (node (ref "C13") (pin "1") (pinfunction "1_1") (pintype "passive"))
      (node (ref "C15") (pin "1") (pinfunction "1_1") (pintype "passive"))
      (node (ref "C17") (pin "1") (pinfunction "1_1") (pintype "passive"))
      (node (ref "C19") (pin "1") (pinfunction "1_1") (pintype "passive"))
      (node (ref "C21") (pin "1") (pinfunction "1_1") (pintype "passive"))
      (node (ref "C23") (pin "1") (pinfunction "1_1") (pintype "passive"))
      (node (ref "C3") (pin "1") (pinfunction "1_1") (pintype "passive"))
      (node (ref "C5") (pin "1") (pinfunction "1_1") (pintype "passive"))
      (node (ref "C7") (pin "1") (pinfunction "1_1") (pintype "passive"))
      (node (ref "C9") (pin "1") (pinfunction "1_1") (pintype "passive"))
      (node (ref "D10") (pin "P$1") (pinfunction "P$1_P$1") (pintype "bidirectional"))
      (node (ref "D11") (pin "P$1") (pinfunction "P$1_P$1") (pintype "bidirectional"))
      (node (ref "D12") (pin "P$1") (pinfunction "P$1_P$1") (pintype "bidirectional"))
      (node (ref "D13") (pin "P$1") (pinfunction "P$1_P$1") (pintype "bidirectional"))
      (node (ref "D14") (pin "P$1") (pinfunction "P$1_P$1") (pintype "bidirectional"))
      (node (ref "D3") (pin "P$1") (pinfunction "P$1_P$1") (pintype "bidirectional"))
      (node (ref "D4") (pin "P$1") (pinfunction "P$1_P$1") (pintype "bidirectional"))
      (node (ref "D5") (pin "P$1") (pinfunction "P$1_P$1") (pintype "bidirectional"))
      (node (ref "D6") (pin "P$1") (pinfunction "P$1_P$1") (pintype "bidirectional"))
      (node (ref "D7") (pin "P$1") (pinfunction "P$1_P$1") (pintype "bidirectional"))
      (node (ref "D8") (pin "P$1") (pinfunction "P$1_P$1") (pintype "bidirectional"))
      (node (ref "D9") (pin "P$1") (pinfunction "P$1_P$1") (pintype "bidirectional"))
      (node (ref "DRIV1") (pin "1") (pinfunction "VCC_1") (pintype "bidirectional"))
      (node (ref "DRIV10") (pin "1") (pinfunction "VCC_1") (pintype "bidirectional"))
      (node (ref "DRIV11") (pin "1") (pinfunction "VCC_1") (pintype "bidirectional"))
      (node (ref "DRIV12") (pin "1") (pinfunction "VCC_1") (pintype "bidirectional"))
      (node (ref "DRIV2") (pin "1") (pinfunction "VCC_1") (pintype "bidirectional"))
      (node (ref "DRIV3") (pin "1") (pinfunction "VCC_1") (pintype "bidirectional"))
      (node (ref "DRIV4") (pin "1") (pinfunction "VCC_1") (pintype "bidirectional"))
      (node (ref "DRIV5") (pin "1") (pinfunction "VCC_1") (pintype "bidirectional"))
      (node (ref "DRIV6") (pin "1") (pinfunction "VCC_1") (pintype "bidirectional"))
      (node (ref "DRIV7") (pin "1") (pinfunction "VCC_1") (pintype "bidirectional"))
      (node (ref "DRIV8") (pin "1") (pinfunction "VCC_1") (pintype "bidirectional"))
      (node (ref "DRIV9") (pin "1") (pinfunction "VCC_1") (pintype "bidirectional"))
      (node (ref "MOS1") (pin "3") (pinfunction "SOURCE_3") (pintype "bidirectional"))
      (node (ref "MOS11") (pin "3") (pinfunction "SOURCE_3") (pintype "bidirectional"))
      (node (ref "MOS13") (pin "3") (pinfunction "SOURCE_3") (pintype "bidirectional"))
      (node (ref "MOS15") (pin "3") (pinfunction "SOURCE_3") (pintype "bidirectional"))
      (node (ref "MOS17") (pin "3") (pinfunction "SOURCE_3") (pintype "bidirectional"))
      (node (ref "MOS19") (pin "3") (pinfunction "SOURCE_3") (pintype "bidirectional"))
      (node (ref "MOS21") (pin "3") (pinfunction "SOURCE_3") (pintype "bidirectional"))
      (node (ref "MOS23") (pin "3") (pinfunction "SOURCE_3") (pintype "bidirectional"))
      (node (ref "MOS3") (pin "3") (pinfunction "SOURCE_3") (pintype "bidirectional"))
      (node (ref "MOS5") (pin "3") (pinfunction "SOURCE_3") (pintype "bidirectional"))
      (node (ref "MOS7") (pin "3") (pinfunction "SOURCE_3") (pintype "bidirectional"))
      (node (ref "MOS9") (pin "3") (pinfunction "SOURCE_3") (pintype "bidirectional"))
      (node (ref "POWER") (pin "12V@1") (pinfunction "12V_12V@1") (pintype "bidirectional"))
      (node (ref "POWER") (pin "12V@10") (pinfunction "12V_12V@10") (pintype "bidirectional"))
      (node (ref "POWER") (pin "12V@11") (pinfunction "12V_12V@11") (pintype "bidirectional"))
      (node (ref "POWER") (pin "12V@12") (pinfunction "12V_12V@12") (pintype "bidirectional"))
      (node (ref "POWER") (pin "12V@2") (pinfunction "12V_12V@2") (pintype "bidirectional"))
      (node (ref "POWER") (pin "12V@3") (pinfunction "12V_12V@3") (pintype "bidirectional"))
      (node (ref "POWER") (pin "12V@4") (pinfunction "12V_12V@4") (pintype "bidirectional"))
      (node (ref "POWER") (pin "12V@5") (pinfunction "12V_12V@5") (pintype "bidirectional"))
      (node (ref "POWER") (pin "12V@6") (pinfunction "12V_12V@6") (pintype "bidirectional"))
      (node (ref "POWER") (pin "12V@7") (pinfunction "12V_12V@7") (pintype "bidirectional"))
      (node (ref "POWER") (pin "12V@8") (pinfunction "12V_12V@8") (pintype "bidirectional"))
      (node (ref "POWER") (pin "12V@9") (pinfunction "12V_12V@9") (pintype "bidirectional"))
      (node (ref "R2") (pin "2") (pinfunction "2_2") (pintype "passive"))
    )
    (net (code "139") (name "unconnected-(STM1-PadPB7)") (class "Default")
      (node (ref "STM1") (pin "PB7") (pinfunction "PB7_PB7") (pintype "bidirectional"))
    )
    (net (code "140") (name "unconnected-(STM1-PadPF0-OSC_IN)") (class "Default")
      (node (ref "STM1") (pin "PF0-OSC_IN") (pinfunction "PF0-OSC_IN_PF0-OSC_IN") (pintype "bidirectional"))
    )
    (net (code "141") (name "unconnected-(STM1-PadPF1-OSC_OUT)") (class "Default")
      (node (ref "STM1") (pin "PF1-OSC_OUT") (pinfunction "PF1-OSC_OUT_PF1-OSC_OUT") (pintype "bidirectional"))
    )
    (net (code "142") (name "unconnected-(STM2-PadPB7)") (class "Default")
      (node (ref "STM2") (pin "PB7") (pinfunction "PB7_PB7") (pintype "bidirectional"))
    )
    (net (code "143") (name "unconnected-(STM2-PadPF0-OSC_IN)") (class "Default")
      (node (ref "STM2") (pin "PF0-OSC_IN") (pinfunction "PF0-OSC_IN_PF0-OSC_IN") (pintype "bidirectional"))
    )
    (net (code "144") (name "unconnected-(STM2-PadPF1-OSC_OUT)") (class "Default")
      (node (ref "STM2") (pin "PF1-OSC_OUT") (pinfunction "PF1-OSC_OUT_PF1-OSC_OUT") (pintype "bidirectional"))
    )
  )
)
